# DUE3DOM_MINI_rev2_21022017-1546.net
KiCad netlist of a schematic drawn in EAGLE
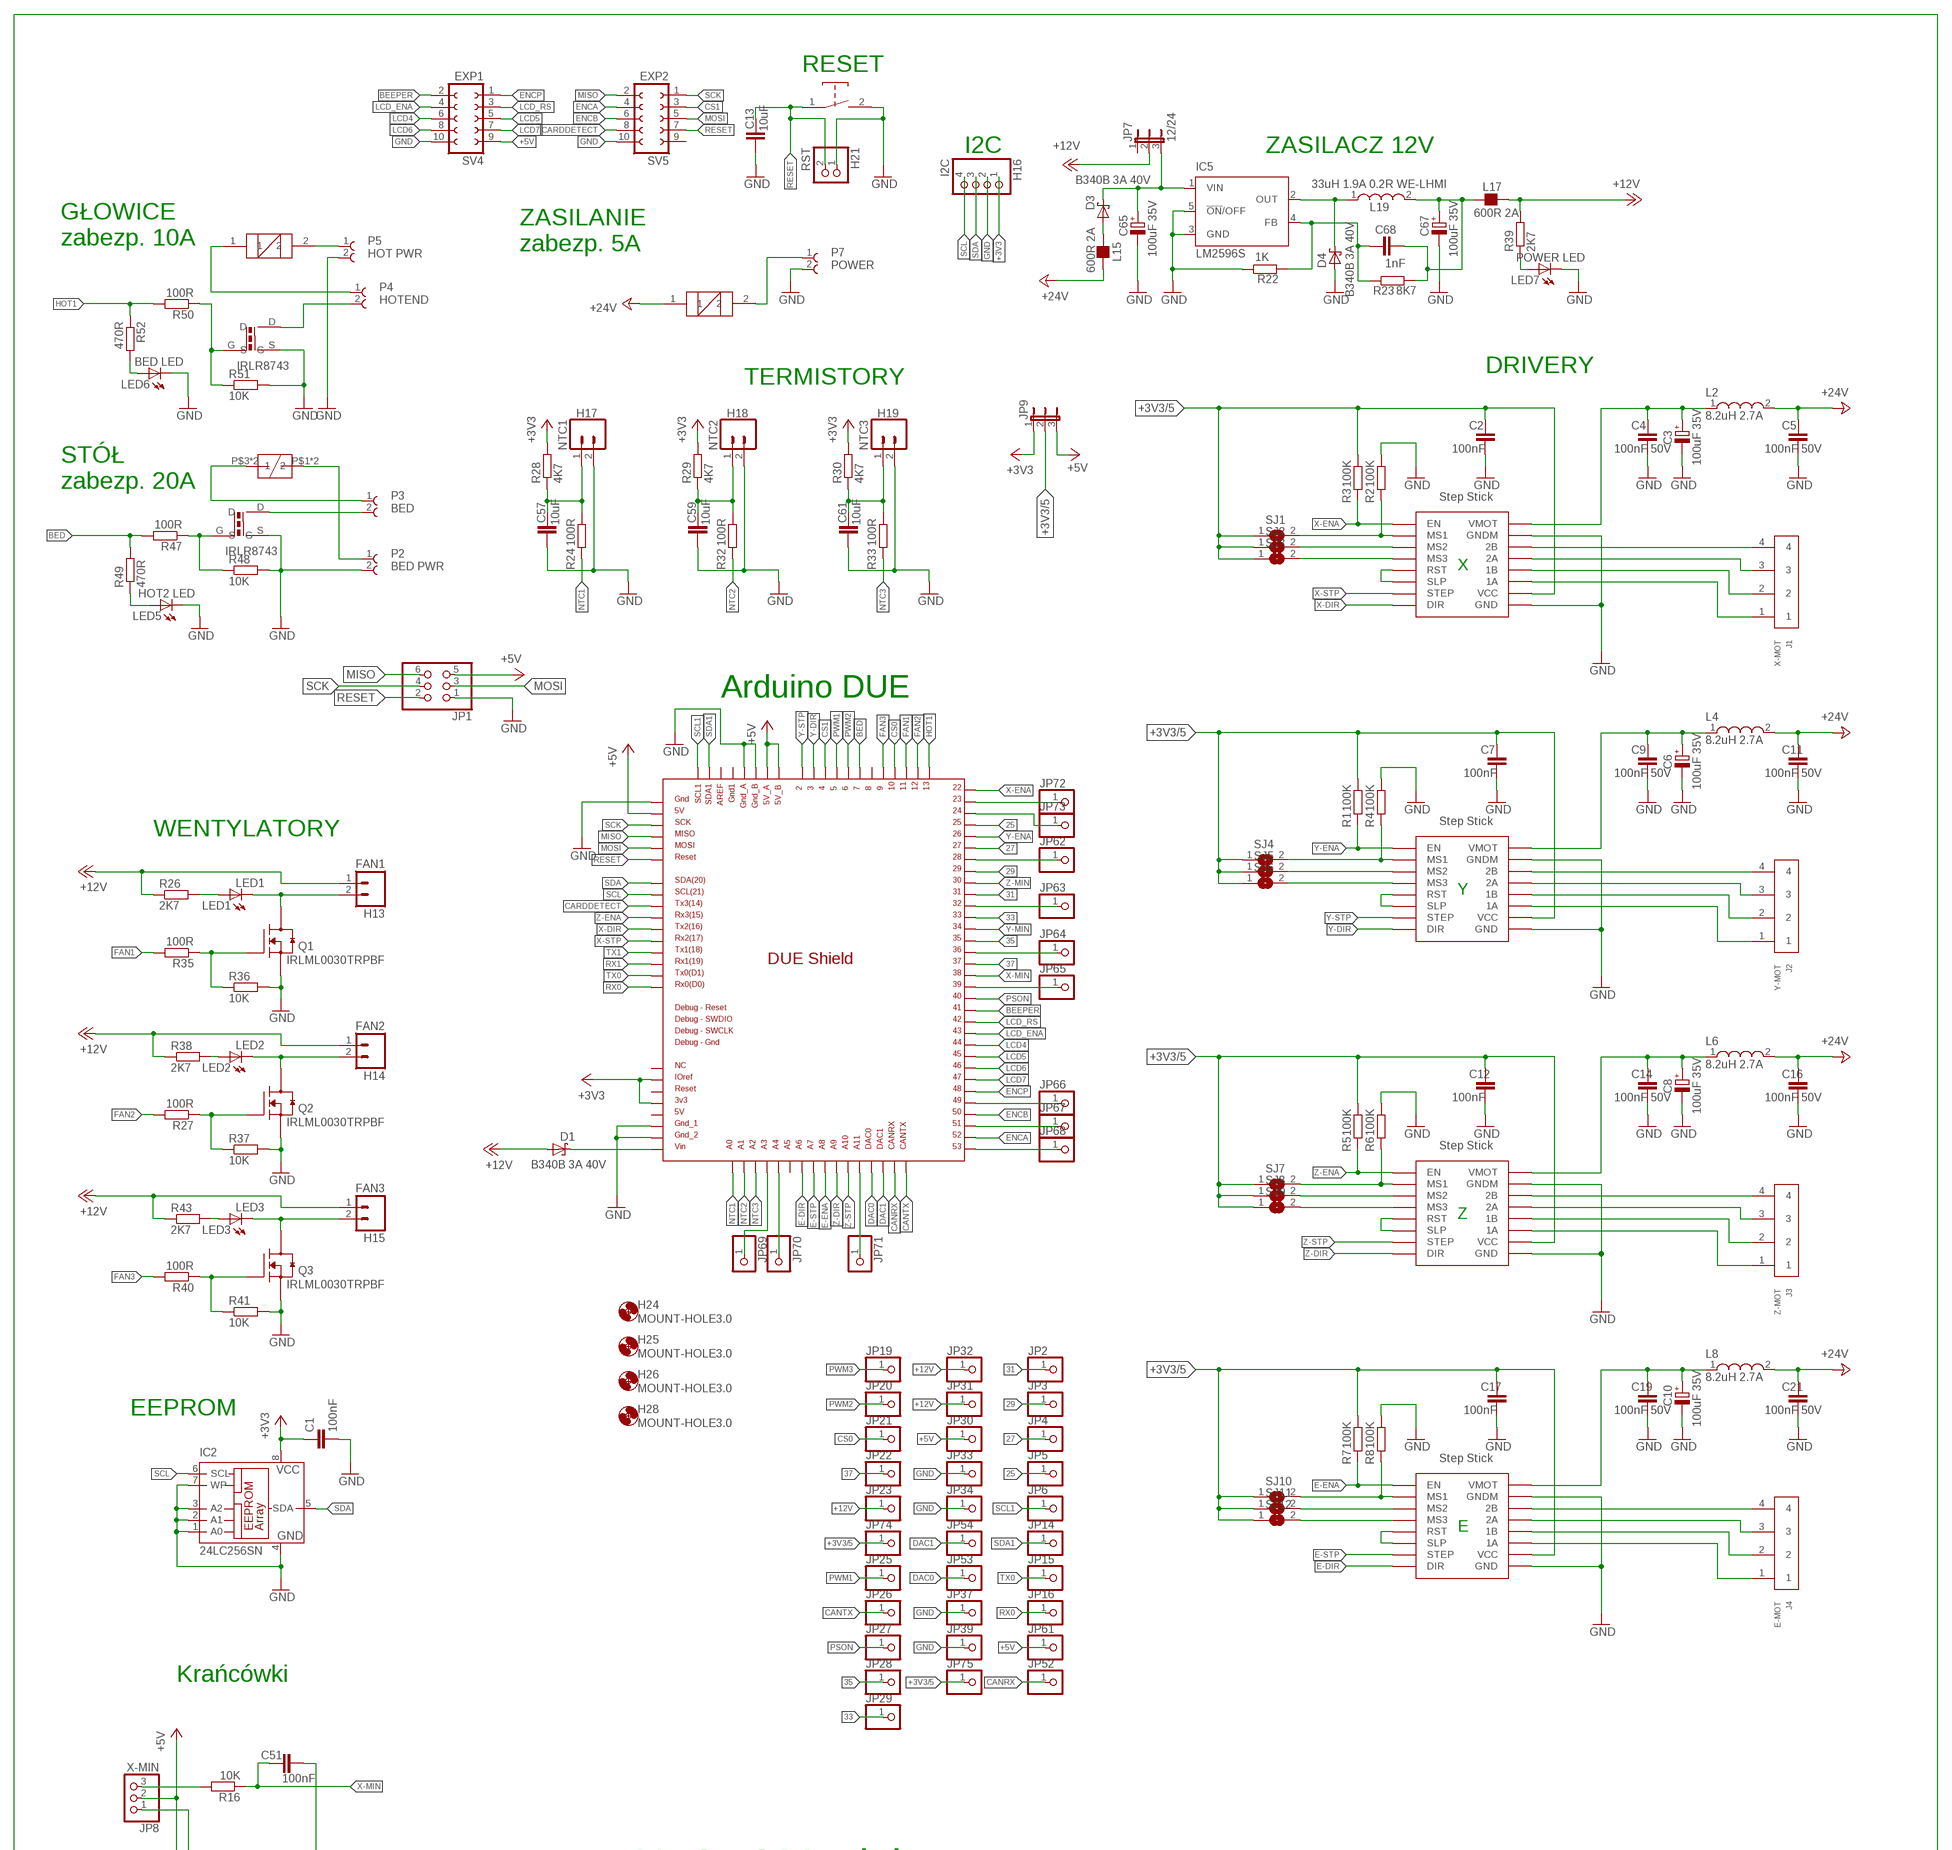
[diagram p0: schematic, sheet 1, part 1 of 2]
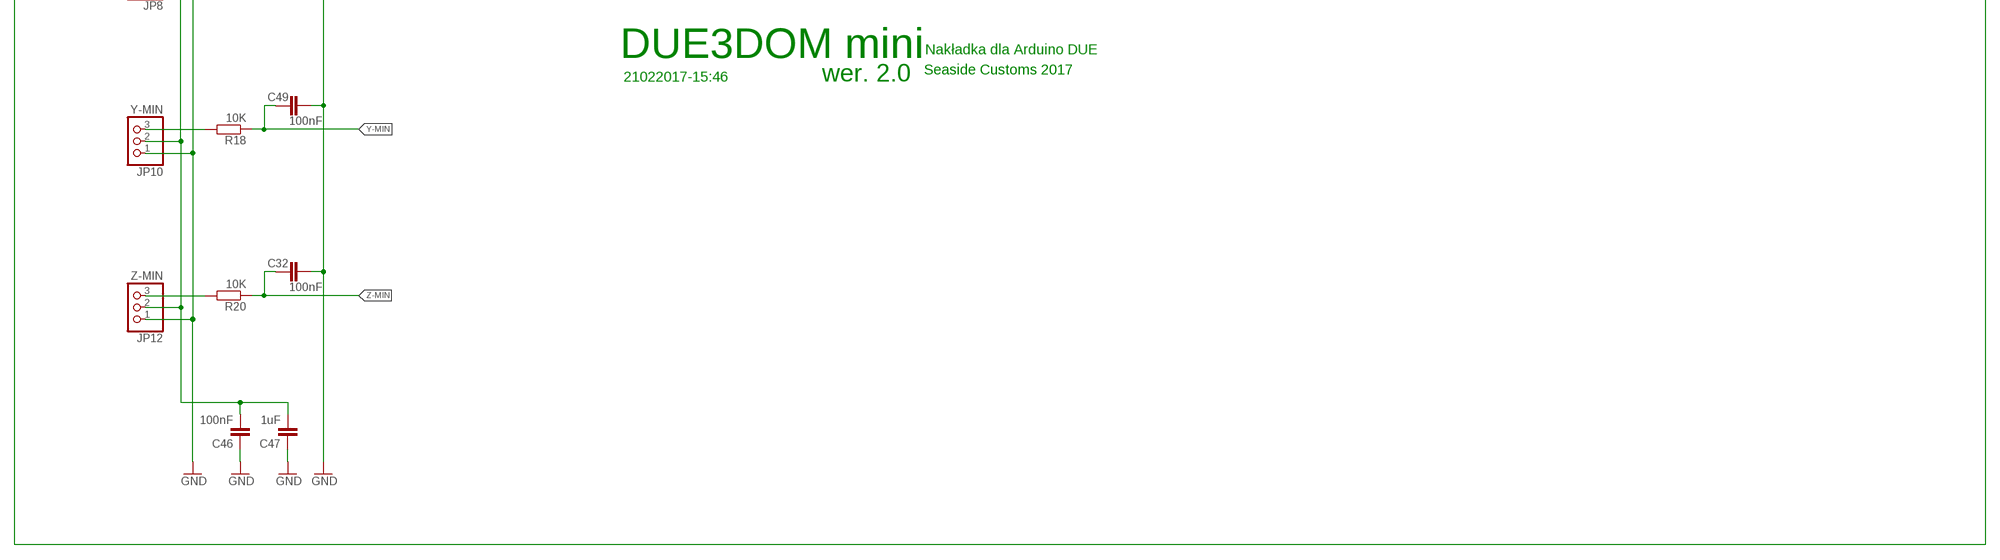
[diagram p1: schematic, sheet 1, part 2 of 2]

(export (version "E")
  (design (tool "Eeschema 10.0.6"))
  (components
    (comp (ref "C1")
      (value "100nF")
      (footprint "eagle-import:C0805")
      (libsource (lib "eagle-import") (part "C-EUC0805"))
    )
    (comp (ref "C2")
      (value "100nF")
      (footprint "eagle-import:C0805")
      (libsource (lib "eagle-import") (part "C-EUC0805"))
    )
    (comp (ref "C3")
      (value "100uF 35V")
      (footprint "eagle-import:PANASONIC_D")
      (libsource (lib "eagle-import") (part "CPOL-EUD"))
    )
    (comp (ref "C4")
      (value "100nF 50V")
      (footprint "eagle-import:C0805")
      (libsource (lib "eagle-import") (part "C-EUC0805"))
    )
    (comp (ref "C5")
      (value "100nF 50V")
      (footprint "eagle-import:C0805")
      (libsource (lib "eagle-import") (part "C-EUC0805"))
    )
    (comp (ref "C6")
      (value "100uF 35V")
      (footprint "eagle-import:PANASONIC_D")
      (libsource (lib "eagle-import") (part "CPOL-EUD"))
    )
    (comp (ref "C7")
      (value "100nF")
      (footprint "eagle-import:C0805")
      (libsource (lib "eagle-import") (part "C-EUC0805"))
    )
    (comp (ref "C8")
      (value "100uF 35V")
      (footprint "eagle-import:PANASONIC_D")
      (libsource (lib "eagle-import") (part "CPOL-EUD"))
    )
    (comp (ref "C9")
      (value "100nF 50V")
      (footprint "eagle-import:C0805")
      (libsource (lib "eagle-import") (part "C-EUC0805"))
    )
    (comp (ref "C10")
      (value "100uF 35V")
      (footprint "eagle-import:PANASONIC_D")
      (libsource (lib "eagle-import") (part "CPOL-EUD"))
    )
    (comp (ref "C11")
      (value "100nF 50V")
      (footprint "eagle-import:C0805")
      (libsource (lib "eagle-import") (part "C-EUC0805"))
    )
    (comp (ref "C12")
      (value "100nF")
      (footprint "eagle-import:C0805")
      (libsource (lib "eagle-import") (part "C-EUC0805"))
    )
    (comp (ref "C13")
      (value "10uF")
      (footprint "eagle-import:C0805")
      (libsource (lib "eagle-import") (part "C-EUC0805"))
    )
    (comp (ref "C14")
      (value "100nF 50V")
      (footprint "eagle-import:C0805")
      (libsource (lib "eagle-import") (part "C-EUC0805"))
    )
    (comp (ref "C16")
      (value "100nF 50V")
      (footprint "eagle-import:C0805")
      (libsource (lib "eagle-import") (part "C-EUC0805"))
    )
    (comp (ref "C17")
      (value "100nF")
      (footprint "eagle-import:C0805")
      (libsource (lib "eagle-import") (part "C-EUC0805"))
    )
    (comp (ref "C19")
      (value "100nF 50V")
      (footprint "eagle-import:C0805")
      (libsource (lib "eagle-import") (part "C-EUC0805"))
    )
    (comp (ref "C21")
      (value "100nF 50V")
      (footprint "eagle-import:C0805")
      (libsource (lib "eagle-import") (part "C-EUC0805"))
    )
    (comp (ref "C32")
      (value "100nF")
      (footprint "eagle-import:C0805")
      (libsource (lib "eagle-import") (part "C-EUC0805"))
    )
    (comp (ref "C46")
      (value "100nF")
      (footprint "eagle-import:C0805")
      (libsource (lib "eagle-import") (part "C-EUC0805"))
    )
    (comp (ref "C47")
      (value "1uF")
      (footprint "eagle-import:C0805")
      (libsource (lib "eagle-import") (part "C-EUC0805"))
    )
    (comp (ref "C49")
      (value "100nF")
      (footprint "eagle-import:C0805")
      (libsource (lib "eagle-import") (part "C-EUC0805"))
    )
    (comp (ref "C51")
      (value "100nF")
      (footprint "eagle-import:C0805")
      (libsource (lib "eagle-import") (part "C-EUC0805"))
    )
    (comp (ref "C57")
      (value "10uF")
      (footprint "eagle-import:C0805")
      (libsource (lib "eagle-import") (part "C-EUC0805"))
    )
    (comp (ref "C59")
      (value "10uF")
      (footprint "eagle-import:C0805")
      (libsource (lib "eagle-import") (part "C-EUC0805"))
    )
    (comp (ref "C61")
      (value "10uF")
      (footprint "eagle-import:C0805")
      (libsource (lib "eagle-import") (part "C-EUC0805"))
    )
    (comp (ref "C65")
      (value "100uF 35V")
      (footprint "eagle-import:E2,5-6")
      (libsource (lib "eagle-import") (part "CPOL-EUE2.5-6"))
    )
    (comp (ref "C67")
      (value "100uF 35V")
      (footprint "eagle-import:E2,5-6")
      (libsource (lib "eagle-import") (part "CPOL-EUE2.5-6"))
    )
    (comp (ref "C68")
      (value "1nF")
      (footprint "eagle-import:C0805")
      (libsource (lib "eagle-import") (part "C-EUC0805"))
    )
    (comp (ref "D1")
      (value "B340B 3A 40V")
      (footprint "eagle-import:SMB")
      (libsource (lib "eagle-import") (part "SCHOTTKY-DIODESMD"))
    )
    (comp (ref "D3")
      (value "B340B 3A 40V")
      (footprint "eagle-import:SMB")
      (libsource (lib "eagle-import") (part "SCHOTTKY-DIODESMD"))
    )
    (comp (ref "D4")
      (value "B340B 3A 40V")
      (footprint "eagle-import:SMB")
      (libsource (lib "eagle-import") (part "SCHOTTKY-DIODESMD"))
    )
    (comp (ref "FET1")
      (value "DPAK_N-CHANNEL_MOSFET")
      (footprint "eagle-import:DPAK_N-CHANNEL_MOSFET")
      (libsource (lib "eagle-import") (part "DPAK_N-CHANNEL_MOSFET"))
    )
    (comp (ref "FET2")
      (value "DPAK_N-CHANNEL_MOSFET")
      (footprint "eagle-import:DPAK_N-CHANNEL_MOSFET")
      (libsource (lib "eagle-import") (part "DPAK_N-CHANNEL_MOSFET"))
    )
    (comp (ref "FUSE")
      (value "GNIAZDO_BEZPIECZNIKA_MINI_CHRL")
      (footprint "eagle-import:FUSE_MINI_CHRL")
      (libsource (lib "eagle-import") (part "GNIAZDO_BEZPIECZNIKA_MINI_CHRL"))
    )
    (comp (ref "H13")
      (value "FAN1")
      (footprint "eagle-import:MOLEX-1X2")
      (libsource (lib "eagle-import") (part "M02POLAR"))
    )
    (comp (ref "H14")
      (value "FAN2")
      (footprint "eagle-import:MOLEX-1X2")
      (libsource (lib "eagle-import") (part "M02POLAR"))
    )
    (comp (ref "H15")
      (value "FAN3")
      (footprint "eagle-import:MOLEX-1X2")
      (libsource (lib "eagle-import") (part "M02POLAR"))
    )
    (comp (ref "H16")
      (value "I2C")
      (footprint "eagle-import:1X04")
      (libsource (lib "eagle-import") (part "PINHD-1X4"))
    )
    (comp (ref "H17")
      (value "NTC1")
      (footprint "eagle-import:MOLEX-1X2")
      (libsource (lib "eagle-import") (part "M02POLAR"))
    )
    (comp (ref "H18")
      (value "NTC2")
      (footprint "eagle-import:MOLEX-1X2")
      (libsource (lib "eagle-import") (part "M02POLAR"))
    )
    (comp (ref "H19")
      (value "NTC3")
      (footprint "eagle-import:MOLEX-1X2")
      (libsource (lib "eagle-import") (part "M02POLAR"))
    )
    (comp (ref "H21")
      (value "RST")
      (footprint "eagle-import:1X02")
      (libsource (lib "eagle-import") (part "PINHD-1X2"))
    )
    (comp (ref "H24")
      (value "MOUNT-HOLE3.0")
      (footprint "eagle-import:3,0")
      (libsource (lib "eagle-import") (part "MOUNT-HOLE3.0"))
    )
    (comp (ref "H25")
      (value "MOUNT-HOLE3.0")
      (footprint "eagle-import:3,0")
      (libsource (lib "eagle-import") (part "MOUNT-HOLE3.0"))
    )
    (comp (ref "H26")
      (value "MOUNT-HOLE3.0")
      (footprint "eagle-import:3,0")
      (libsource (lib "eagle-import") (part "MOUNT-HOLE3.0"))
    )
    (comp (ref "H28")
      (value "MOUNT-HOLE3.0")
      (footprint "eagle-import:3,0")
      (libsource (lib "eagle-import") (part "MOUNT-HOLE3.0"))
    )
    (comp (ref "IC2")
      (value "24LC256SN")
      (footprint "eagle-import:SO-08")
      (fields (field (name "MF") "MICROCHIP") (field (name "MPN") "24LC256-I/SN"))
      (libsource (lib "eagle-import") (part "24SNLC256"))
    )
    (comp (ref "IC5")
      (value "LM2596S")
      (footprint "eagle-import:TO263-5")
      (fields (field (name "MF") "NATIONAL SEMICONDUCTOR") (field (name "MPN") "LM2596S-ADJ/NOPB"))
      (libsource (lib "eagle-import") (part "LM2596S"))
    )
    (comp (ref "J1")
      (value "X-MOT")
      (footprint "eagle-import:66100411622")
      (libsource (lib "eagle-import") (part "66100411622"))
    )
    (comp (ref "J2")
      (value "Y-MOT")
      (footprint "eagle-import:66100411622")
      (libsource (lib "eagle-import") (part "66100411622"))
    )
    (comp (ref "J3")
      (value "Z-MOT")
      (footprint "eagle-import:66100411622")
      (libsource (lib "eagle-import") (part "66100411622"))
    )
    (comp (ref "J4")
      (value "E-MOT")
      (footprint "eagle-import:66100411622")
      (libsource (lib "eagle-import") (part "66100411622"))
    )
    (comp (ref "JP1")
      (value "PINHD-2X3")
      (footprint "eagle-import:2X03")
      (libsource (lib "eagle-import") (part "PINHD-2X3"))
    )
    (comp (ref "JP2")
      (value "PINHD-1X1")
      (footprint "eagle-import:1X01")
      (libsource (lib "eagle-import") (part "PINHD-1X1"))
    )
    (comp (ref "JP3")
      (value "PINHD-1X1")
      (footprint "eagle-import:1X01")
      (libsource (lib "eagle-import") (part "PINHD-1X1"))
    )
    (comp (ref "JP4")
      (value "PINHD-1X1")
      (footprint "eagle-import:1X01")
      (libsource (lib "eagle-import") (part "PINHD-1X1"))
    )
    (comp (ref "JP5")
      (value "PINHD-1X1")
      (footprint "eagle-import:1X01")
      (libsource (lib "eagle-import") (part "PINHD-1X1"))
    )
    (comp (ref "JP6")
      (value "PINHD-1X1")
      (footprint "eagle-import:1X01")
      (libsource (lib "eagle-import") (part "PINHD-1X1"))
    )
    (comp (ref "JP7")
      (value "12/24")
      (footprint "eagle-import:JP2")
      (libsource (lib "eagle-import") (part "JP2E"))
    )
    (comp (ref "JP8")
      (value "X-MIN")
      (footprint "eagle-import:1X03")
      (libsource (lib "eagle-import") (part "PINHD-1X3"))
    )
    (comp (ref "JP9")
      (value "JP2E")
      (footprint "eagle-import:JP2")
      (libsource (lib "eagle-import") (part "JP2E"))
    )
    (comp (ref "JP10")
      (value "Y-MIN")
      (footprint "eagle-import:1X03")
      (libsource (lib "eagle-import") (part "PINHD-1X3"))
    )
    (comp (ref "JP12")
      (value "Z-MIN")
      (footprint "eagle-import:1X03")
      (libsource (lib "eagle-import") (part "PINHD-1X3"))
    )
    (comp (ref "JP14")
      (value "PINHD-1X1")
      (footprint "eagle-import:1X01")
      (libsource (lib "eagle-import") (part "PINHD-1X1"))
    )
    (comp (ref "JP15")
      (value "PINHD-1X1")
      (footprint "eagle-import:1X01")
      (libsource (lib "eagle-import") (part "PINHD-1X1"))
    )
    (comp (ref "JP16")
      (value "PINHD-1X1")
      (footprint "eagle-import:1X01")
      (libsource (lib "eagle-import") (part "PINHD-1X1"))
    )
    (comp (ref "JP19")
      (value "PINHD-1X1")
      (footprint "eagle-import:1X01")
      (libsource (lib "eagle-import") (part "PINHD-1X1"))
    )
    (comp (ref "JP20")
      (value "PINHD-1X1")
      (footprint "eagle-import:1X01")
      (libsource (lib "eagle-import") (part "PINHD-1X1"))
    )
    (comp (ref "JP21")
      (value "PINHD-1X1")
      (footprint "eagle-import:1X01")
      (libsource (lib "eagle-import") (part "PINHD-1X1"))
    )
    (comp (ref "JP22")
      (value "PINHD-1X1")
      (footprint "eagle-import:1X01")
      (libsource (lib "eagle-import") (part "PINHD-1X1"))
    )
    (comp (ref "JP23")
      (value "PINHD-1X1")
      (footprint "eagle-import:1X01")
      (libsource (lib "eagle-import") (part "PINHD-1X1"))
    )
    (comp (ref "JP25")
      (value "PINHD-1X1")
      (footprint "eagle-import:1X01")
      (libsource (lib "eagle-import") (part "PINHD-1X1"))
    )
    (comp (ref "JP26")
      (value "PINHD-1X1")
      (footprint "eagle-import:1X01")
      (libsource (lib "eagle-import") (part "PINHD-1X1"))
    )
    (comp (ref "JP27")
      (value "PINHD-1X1")
      (footprint "eagle-import:1X01")
      (libsource (lib "eagle-import") (part "PINHD-1X1"))
    )
    (comp (ref "JP28")
      (value "PINHD-1X1")
      (footprint "eagle-import:1X01")
      (libsource (lib "eagle-import") (part "PINHD-1X1"))
    )
    (comp (ref "JP29")
      (value "PINHD-1X1")
      (footprint "eagle-import:1X01")
      (libsource (lib "eagle-import") (part "PINHD-1X1"))
    )
    (comp (ref "JP30")
      (value "PINHD-1X1")
      (footprint "eagle-import:1X01")
      (libsource (lib "eagle-import") (part "PINHD-1X1"))
    )
    (comp (ref "JP31")
      (value "PINHD-1X1")
      (footprint "eagle-import:1X01")
      (libsource (lib "eagle-import") (part "PINHD-1X1"))
    )
    (comp (ref "JP32")
      (value "PINHD-1X1")
      (footprint "eagle-import:1X01")
      (libsource (lib "eagle-import") (part "PINHD-1X1"))
    )
    (comp (ref "JP33")
      (value "PINHD-1X1")
      (footprint "eagle-import:1X01")
      (libsource (lib "eagle-import") (part "PINHD-1X1"))
    )
    (comp (ref "JP34")
      (value "PINHD-1X1")
      (footprint "eagle-import:1X01")
      (libsource (lib "eagle-import") (part "PINHD-1X1"))
    )
    (comp (ref "JP37")
      (value "PINHD-1X1")
      (footprint "eagle-import:1X01")
      (libsource (lib "eagle-import") (part "PINHD-1X1"))
    )
    (comp (ref "JP39")
      (value "PINHD-1X1")
      (footprint "eagle-import:1X01")
      (libsource (lib "eagle-import") (part "PINHD-1X1"))
    )
    (comp (ref "JP52")
      (value "PINHD-1X1")
      (footprint "eagle-import:1X01")
      (libsource (lib "eagle-import") (part "PINHD-1X1"))
    )
    (comp (ref "JP53")
      (value "PINHD-1X1")
      (footprint "eagle-import:1X01")
      (libsource (lib "eagle-import") (part "PINHD-1X1"))
    )
    (comp (ref "JP54")
      (value "PINHD-1X1")
      (footprint "eagle-import:1X01")
      (libsource (lib "eagle-import") (part "PINHD-1X1"))
    )
    (comp (ref "JP61")
      (value "PINHD-1X1")
      (footprint "eagle-import:1X01")
      (libsource (lib "eagle-import") (part "PINHD-1X1"))
    )
    (comp (ref "JP62")
      (value "PINHD-1X1")
      (footprint "eagle-import:1X01")
      (libsource (lib "eagle-import") (part "PINHD-1X1"))
    )
    (comp (ref "JP63")
      (value "PINHD-1X1")
      (footprint "eagle-import:1X01")
      (libsource (lib "eagle-import") (part "PINHD-1X1"))
    )
    (comp (ref "JP64")
      (value "PINHD-1X1")
      (footprint "eagle-import:1X01")
      (libsource (lib "eagle-import") (part "PINHD-1X1"))
    )
    (comp (ref "JP65")
      (value "PINHD-1X1")
      (footprint "eagle-import:1X01")
      (libsource (lib "eagle-import") (part "PINHD-1X1"))
    )
    (comp (ref "JP66")
      (value "PINHD-1X1")
      (footprint "eagle-import:1X01")
      (libsource (lib "eagle-import") (part "PINHD-1X1"))
    )
    (comp (ref "JP67")
      (value "PINHD-1X1")
      (footprint "eagle-import:1X01")
      (libsource (lib "eagle-import") (part "PINHD-1X1"))
    )
    (comp (ref "JP68")
      (value "PINHD-1X1")
      (footprint "eagle-import:1X01")
      (libsource (lib "eagle-import") (part "PINHD-1X1"))
    )
    (comp (ref "JP69")
      (value "PINHD-1X1")
      (footprint "eagle-import:1X01")
      (libsource (lib "eagle-import") (part "PINHD-1X1"))
    )
    (comp (ref "JP70")
      (value "PINHD-1X1")
      (footprint "eagle-import:1X01")
      (libsource (lib "eagle-import") (part "PINHD-1X1"))
    )
    (comp (ref "JP71")
      (value "PINHD-1X1")
      (footprint "eagle-import:1X01")
      (libsource (lib "eagle-import") (part "PINHD-1X1"))
    )
    (comp (ref "JP72")
      (value "PINHD-1X1")
      (footprint "eagle-import:1X01")
      (libsource (lib "eagle-import") (part "PINHD-1X1"))
    )
    (comp (ref "JP73")
      (value "PINHD-1X1")
      (footprint "eagle-import:1X01")
      (libsource (lib "eagle-import") (part "PINHD-1X1"))
    )
    (comp (ref "JP74")
      (value "PINHD-1X1")
      (footprint "eagle-import:1X01")
      (libsource (lib "eagle-import") (part "PINHD-1X1"))
    )
    (comp (ref "JP75")
      (value "PINHD-1X1")
      (footprint "eagle-import:1X01")
      (libsource (lib "eagle-import") (part "PINHD-1X1"))
    )
    (comp (ref "L2")
      (value "8.2uH 2.7A")
      (footprint "eagle-import:WE-PD_7332_7345_PLASTIC_BASE")
      (libsource (lib "eagle-import") (part "WE-PD_7332/7345_PLASTIC_BASE"))
    )
    (comp (ref "L4")
      (value "8.2uH 2.7A")
      (footprint "eagle-import:WE-PD_7332_7345_PLASTIC_BASE")
      (libsource (lib "eagle-import") (part "WE-PD_7332/7345_PLASTIC_BASE"))
    )
    (comp (ref "L6")
      (value "8.2uH 2.7A")
      (footprint "eagle-import:WE-PD_7332_7345_PLASTIC_BASE")
      (libsource (lib "eagle-import") (part "WE-PD_7332/7345_PLASTIC_BASE"))
    )
    (comp (ref "L8")
      (value "8.2uH 2.7A")
      (footprint "eagle-import:WE-PD_7332_7345_PLASTIC_BASE")
      (libsource (lib "eagle-import") (part "WE-PD_7332/7345_PLASTIC_BASE"))
    )
    (comp (ref "L15")
      (value "600R 2A")
      (footprint "eagle-import:L1206")
      (libsource (lib "eagle-import") (part "FB_1206"))
    )
    (comp (ref "L17")
      (value "600R 2A")
      (footprint "eagle-import:L1206")
      (libsource (lib "eagle-import") (part "FB_1206"))
    )
    (comp (ref "L19")
      (value "33uH 1.9A 0.2R WE-LHMI")
      (footprint "eagle-import:WE-LHMI_7030_7050")
      (libsource (lib "eagle-import") (part "WE-LHMI_7030/7050"))
    )
    (comp (ref "LED1")
      (value "LED1")
      (footprint "eagle-import:LED_0805_BIVAR_VLP-250-F")
      (libsource (lib "eagle-import") (part "LED_0805_BIVAR_VLP-250-F"))
    )
    (comp (ref "LED2")
      (value "LED2")
      (footprint "eagle-import:LED_0805_BIVAR_VLP-250-F")
      (libsource (lib "eagle-import") (part "LED_0805_BIVAR_VLP-250-F"))
    )
    (comp (ref "LED3")
      (value "LED3")
      (footprint "eagle-import:LED_0805_BIVAR_VLP-250-F")
      (libsource (lib "eagle-import") (part "LED_0805_BIVAR_VLP-250-F"))
    )
    (comp (ref "LED5")
      (value "HOT2 LED")
      (footprint "eagle-import:LED_0805_BIVAR_VLP-250-F")
      (libsource (lib "eagle-import") (part "LED_0805_BIVAR_VLP-250-F"))
    )
    (comp (ref "LED6")
      (value "BED LED")
      (footprint "eagle-import:LED_0805_BIVAR_VLP-250-F")
      (libsource (lib "eagle-import") (part "LED_0805_BIVAR_VLP-250-F"))
    )
    (comp (ref "LED7")
      (value "POWER LED")
      (footprint "eagle-import:LED_0805_BIVAR_VLP-250-F")
      (libsource (lib "eagle-import") (part "LED_0805_BIVAR_VLP-250-F"))
    )
    (comp (ref "P2")
      (value "BED PWR")
      (footprint "eagle-import:691241710002")
      (libsource (lib "eagle-import") (part "691241710002"))
    )
    (comp (ref "P3")
      (value "BED")
      (footprint "eagle-import:691241710002")
      (libsource (lib "eagle-import") (part "691241710002"))
    )
    (comp (ref "P4")
      (value "HOTEND")
      (footprint "eagle-import:691241710002")
      (libsource (lib "eagle-import") (part "691241710002"))
    )
    (comp (ref "P5")
      (value "HOT PWR")
      (footprint "eagle-import:691241710002")
      (libsource (lib "eagle-import") (part "691241710002"))
    )
    (comp (ref "P7")
      (value "POWER")
      (footprint "eagle-import:691241710002")
      (libsource (lib "eagle-import") (part "691241710002"))
    )
    (comp (ref "Q1")
      (value "IRLML0030TRPBF")
      (footprint "eagle-import:SOT95P280X135-3N")
      (libsource (lib "eagle-import") (part "MOSFET-NCH_SOT-23"))
    )
    (comp (ref "Q2")
      (value "IRLML0030TRPBF")
      (footprint "eagle-import:SOT95P280X135-3N")
      (libsource (lib "eagle-import") (part "MOSFET-NCH_SOT-23"))
    )
    (comp (ref "Q3")
      (value "IRLML0030TRPBF")
      (footprint "eagle-import:SOT95P280X135-3N")
      (libsource (lib "eagle-import") (part "MOSFET-NCH_SOT-23"))
    )
    (comp (ref "R1")
      (value "100K")
      (footprint "eagle-import:R0805")
      (libsource (lib "eagle-import") (part "R-EU_R0805"))
    )
    (comp (ref "R2")
      (value "100K")
      (footprint "eagle-import:R0805")
      (libsource (lib "eagle-import") (part "R-EU_R0805"))
    )
    (comp (ref "R3")
      (value "100K")
      (footprint "eagle-import:R0805")
      (libsource (lib "eagle-import") (part "R-EU_R0805"))
    )
    (comp (ref "R4")
      (value "100K")
      (footprint "eagle-import:R0805")
      (libsource (lib "eagle-import") (part "R-EU_R0805"))
    )
    (comp (ref "R5")
      (value "100K")
      (footprint "eagle-import:R0805")
      (libsource (lib "eagle-import") (part "R-EU_R0805"))
    )
    (comp (ref "R6")
      (value "100K")
      (footprint "eagle-import:R0805")
      (libsource (lib "eagle-import") (part "R-EU_R0805"))
    )
    (comp (ref "R7")
      (value "100K")
      (footprint "eagle-import:R0805")
      (libsource (lib "eagle-import") (part "R-EU_R0805"))
    )
    (comp (ref "R8")
      (value "100K")
      (footprint "eagle-import:R0805")
      (libsource (lib "eagle-import") (part "R-EU_R0805"))
    )
    (comp (ref "R16")
      (value "10K")
      (footprint "eagle-import:R0805")
      (libsource (lib "eagle-import") (part "R-EU_R0805"))
    )
    (comp (ref "R18")
      (value "10K")
      (footprint "eagle-import:R0805")
      (libsource (lib "eagle-import") (part "R-EU_R0805"))
    )
    (comp (ref "R20")
      (value "10K")
      (footprint "eagle-import:R0805")
      (libsource (lib "eagle-import") (part "R-EU_R0805"))
    )
    (comp (ref "R22")
      (value "1K")
      (footprint "eagle-import:R0805")
      (libsource (lib "eagle-import") (part "R-EU_R0805"))
    )
    (comp (ref "R23")
      (value "8K7")
      (footprint "eagle-import:R0805")
      (libsource (lib "eagle-import") (part "R-EU_R0805"))
    )
    (comp (ref "R24")
      (value "100R")
      (footprint "eagle-import:R0805")
      (libsource (lib "eagle-import") (part "R-EU_R0805"))
    )
    (comp (ref "R26")
      (value "2K7")
      (footprint "eagle-import:R0805")
      (libsource (lib "eagle-import") (part "R-EU_R0805"))
    )
    (comp (ref "R27")
      (value "100R")
      (footprint "eagle-import:R0805")
      (libsource (lib "eagle-import") (part "R-EU_R0805"))
    )
    (comp (ref "R28")
      (value "4K7")
      (footprint "eagle-import:R0805")
      (libsource (lib "eagle-import") (part "R-EU_R0805"))
    )
    (comp (ref "R29")
      (value "4K7")
      (footprint "eagle-import:R0805")
      (libsource (lib "eagle-import") (part "R-EU_R0805"))
    )
    (comp (ref "R30")
      (value "4K7")
      (footprint "eagle-import:R0805")
      (libsource (lib "eagle-import") (part "R-EU_R0805"))
    )
    (comp (ref "R32")
      (value "100R")
      (footprint "eagle-import:R0805")
      (libsource (lib "eagle-import") (part "R-EU_R0805"))
    )
    (comp (ref "R33")
      (value "100R")
      (footprint "eagle-import:R0805")
      (libsource (lib "eagle-import") (part "R-EU_R0805"))
    )
    (comp (ref "R35")
      (value "100R")
      (footprint "eagle-import:R0805")
      (libsource (lib "eagle-import") (part "R-EU_R0805"))
    )
    (comp (ref "R36")
      (value "10K")
      (footprint "eagle-import:R0805")
      (libsource (lib "eagle-import") (part "R-EU_R0805"))
    )
    (comp (ref "R37")
      (value "10K")
      (footprint "eagle-import:R0805")
      (libsource (lib "eagle-import") (part "R-EU_R0805"))
    )
    (comp (ref "R38")
      (value "2K7")
      (footprint "eagle-import:R0805")
      (libsource (lib "eagle-import") (part "R-EU_R0805"))
    )
    (comp (ref "R39")
      (value "2K7")
      (footprint "eagle-import:R0805")
      (libsource (lib "eagle-import") (part "R-EU_R0805"))
    )
    (comp (ref "R40")
      (value "100R")
      (footprint "eagle-import:R0805")
      (libsource (lib "eagle-import") (part "R-EU_R0805"))
    )
    (comp (ref "R41")
      (value "10K")
      (footprint "eagle-import:R0805")
      (libsource (lib "eagle-import") (part "R-EU_R0805"))
    )
    (comp (ref "R43")
      (value "2K7")
      (footprint "eagle-import:R0805")
      (libsource (lib "eagle-import") (part "R-EU_R0805"))
    )
    (comp (ref "R47")
      (value "100R")
      (footprint "eagle-import:R0805")
      (libsource (lib "eagle-import") (part "R-EU_R0805"))
    )
    (comp (ref "R48")
      (value "10K")
      (footprint "eagle-import:R0805")
      (libsource (lib "eagle-import") (part "R-EU_R0805"))
    )
    (comp (ref "R49")
      (value "470R")
      (footprint "eagle-import:R0805")
      (libsource (lib "eagle-import") (part "R-EU_R0805"))
    )
    (comp (ref "R50")
      (value "100R")
      (footprint "eagle-import:R0805")
      (libsource (lib "eagle-import") (part "R-EU_R0805"))
    )
    (comp (ref "R51")
      (value "10K")
      (footprint "eagle-import:R0805")
      (libsource (lib "eagle-import") (part "R-EU_R0805"))
    )
    (comp (ref "R52")
      (value "470R")
      (footprint "eagle-import:R0805")
      (libsource (lib "eagle-import") (part "R-EU_R0805"))
    )
    (comp (ref "RESET")
      (value "RESET")
      (footprint "eagle-import:WIDE_TACT")
      (libsource (lib "eagle-import") (part "WIDE_TACT"))
    )
    (comp (ref "SJ1") (value "SJ") (footprint "eagle-import:SJ") (libsource (lib "eagle-import") (part "SJ")))
    (comp (ref "SJ2") (value "SJ") (footprint "eagle-import:SJ") (libsource (lib "eagle-import") (part "SJ")))
    (comp (ref "SJ3") (value "SJ") (footprint "eagle-import:SJ") (libsource (lib "eagle-import") (part "SJ")))
    (comp (ref "SJ4") (value "SJ") (footprint "eagle-import:SJ") (libsource (lib "eagle-import") (part "SJ")))
    (comp (ref "SJ5") (value "SJ") (footprint "eagle-import:SJ") (libsource (lib "eagle-import") (part "SJ")))
    (comp (ref "SJ6") (value "SJ") (footprint "eagle-import:SJ") (libsource (lib "eagle-import") (part "SJ")))
    (comp (ref "SJ7") (value "SJ") (footprint "eagle-import:SJ") (libsource (lib "eagle-import") (part "SJ")))
    (comp (ref "SJ8") (value "SJ") (footprint "eagle-import:SJ") (libsource (lib "eagle-import") (part "SJ")))
    (comp (ref "SJ9") (value "SJ") (footprint "eagle-import:SJ") (libsource (lib "eagle-import") (part "SJ")))
    (comp (ref "SJ10")
      (value "SJ")
      (footprint "eagle-import:SJ")
      (libsource (lib "eagle-import") (part "SJ"))
    )
    (comp (ref "SJ11")
      (value "SJ")
      (footprint "eagle-import:SJ")
      (libsource (lib "eagle-import") (part "SJ"))
    )
    (comp (ref "SJ12")
      (value "SJ")
      (footprint "eagle-import:SJ")
      (libsource (lib "eagle-import") (part "SJ"))
    )
    (comp (ref "STEPSTICK-X")
      (value "STEP-STICK")
      (footprint "eagle-import:STEP-STICK")
      (libsource (lib "eagle-import") (part "STEP-STICK"))
    )
    (comp (ref "STEPSTICK-Y")
      (value "STEP-STICK")
      (footprint "eagle-import:STEP-STICK")
      (libsource (lib "eagle-import") (part "STEP-STICK"))
    )
    (comp (ref "STEPSTICK-Z1")
      (value "STEP-STICK")
      (footprint "eagle-import:STEP-STICK")
      (libsource (lib "eagle-import") (part "STEP-STICK"))
    )
    (comp (ref "STEPSTICK-Z2")
      (value "STEP-STICK")
      (footprint "eagle-import:STEP-STICK")
      (libsource (lib "eagle-import") (part "STEP-STICK"))
    )
    (comp (ref "SV4")
      (value "EXP1")
      (footprint "eagle-import:FE05-2")
      (libsource (lib "eagle-import") (part "FE05-2"))
    )
    (comp (ref "SV5")
      (value "EXP2")
      (footprint "eagle-import:FE05-2")
      (libsource (lib "eagle-import") (part "FE05-2"))
    )
    (comp (ref "U$1")
      (value "DUE(NORMAL)")
      (footprint "eagle-import:DUE(NORMAL)")
      (libsource (lib "eagle-import") (part "DUE(NORMAL)"))
    )
    (comp (ref "U$2")
      (value "FUSE_1808")
      (footprint "eagle-import:FUSE_1808")
      (libsource (lib "eagle-import") (part "FUSE_1808"))
    )
    (comp (ref "U$3")
      (value "FUSE_1808")
      (footprint "eagle-import:FUSE_1808")
      (libsource (lib "eagle-import") (part "FUSE_1808"))
    )
  )
  (nets
    (net (code "1") (name "+3V3") (class "Default")
      (node (ref "C1") (pin "1") (pinfunction "1_1") (pintype "passive"))
      (node (ref "H16") (pin "1") (pinfunction "1_1") (pintype "passive"))
      (node (ref "IC2") (pin "8") (pinfunction "VCC_8") (pintype "power_in"))
      (node (ref "JP9") (pin "1") (pinfunction "1_1") (pintype "passive"))
      (node (ref "R28") (pin "2") (pinfunction "2_2") (pintype "passive"))
      (node (ref "R29") (pin "2") (pinfunction "2_2") (pintype "passive"))
      (node (ref "R30") (pin "2") (pinfunction "2_2") (pintype "passive"))
      (node (ref "U$1") (pin "3V3") (pinfunction "3V3_3V3") (pintype "bidirectional"))
      (node (ref "U$1") (pin "IOREF") (pinfunction "IOREF_IOREF") (pintype "bidirectional"))
    )
    (net (code "2") (name "+3V3{slash}5") (class "Default")
      (node (ref "C12") (pin "1") (pinfunction "1_1") (pintype "passive"))
      (node (ref "C17") (pin "1") (pinfunction "1_1") (pintype "passive"))
      (node (ref "C2") (pin "1") (pinfunction "1_1") (pintype "passive"))
      (node (ref "C7") (pin "1") (pinfunction "1_1") (pintype "passive"))
      (node (ref "JP74") (pin "1") (pinfunction "1_1") (pintype "passive"))
      (node (ref "JP75") (pin "1") (pinfunction "1_1") (pintype "passive"))
      (node (ref "JP9") (pin "2") (pinfunction "2_2") (pintype "passive"))
      (node (ref "R1") (pin "1") (pinfunction "1_1") (pintype "passive"))
      (node (ref "R3") (pin "1") (pinfunction "1_1") (pintype "passive"))
      (node (ref "R5") (pin "1") (pinfunction "1_1") (pintype "passive"))
      (node (ref "R7") (pin "1") (pinfunction "1_1") (pintype "passive"))
      (node (ref "SJ1") (pin "1") (pinfunction "1_1") (pintype "passive"))
      (node (ref "SJ10") (pin "1") (pinfunction "1_1") (pintype "passive"))
      (node (ref "SJ11") (pin "1") (pinfunction "1_1") (pintype "passive"))
      (node (ref "SJ12") (pin "1") (pinfunction "1_1") (pintype "passive"))
      (node (ref "SJ2") (pin "1") (pinfunction "1_1") (pintype "passive"))
      (node (ref "SJ3") (pin "1") (pinfunction "1_1") (pintype "passive"))
      (node (ref "SJ4") (pin "1") (pinfunction "1_1") (pintype "passive"))
      (node (ref "SJ5") (pin "1") (pinfunction "1_1") (pintype "passive"))
      (node (ref "SJ6") (pin "1") (pinfunction "1_1") (pintype "passive"))
      (node (ref "SJ7") (pin "1") (pinfunction "1_1") (pintype "passive"))
      (node (ref "SJ8") (pin "1") (pinfunction "1_1") (pintype "passive"))
      (node (ref "SJ9") (pin "1") (pinfunction "1_1") (pintype "passive"))
      (node (ref "STEPSTICK-X") (pin "VDD") (pinfunction "VCC_VDD") (pintype "bidirectional"))
      (node (ref "STEPSTICK-Y") (pin "VDD") (pinfunction "VCC_VDD") (pintype "bidirectional"))
      (node (ref "STEPSTICK-Z1") (pin "VDD") (pinfunction "VCC_VDD") (pintype "bidirectional"))
      (node (ref "STEPSTICK-Z2") (pin "VDD") (pinfunction "VCC_VDD") (pintype "bidirectional"))
    )
    (net (code "3") (name "+5V") (class "Default")
      (node (ref "C46") (pin "2") (pinfunction "2_2") (pintype "passive"))
      (node (ref "C47") (pin "2") (pinfunction "2_2") (pintype "passive"))
      (node (ref "JP1") (pin "5") (pinfunction "5_5") (pintype "passive"))
      (node (ref "JP10") (pin "2") (pinfunction "2_2") (pintype "passive"))
      (node (ref "JP12") (pin "2") (pinfunction "2_2") (pintype "passive"))
      (node (ref "JP30") (pin "1") (pinfunction "1_1") (pintype "passive"))
      (node (ref "JP61") (pin "1") (pinfunction "1_1") (pintype "passive"))
      (node (ref "JP8") (pin "2") (pinfunction "2_2") (pintype "passive"))
      (node (ref "JP9") (pin "3") (pinfunction "3_3") (pintype "passive"))
      (node (ref "SV4") (pin "9") (pinfunction "9_9") (pintype "passive"))
      (node (ref "U$1") (pin "5V_A") (pinfunction "5V_A_5V_A") (pintype "bidirectional"))
      (node (ref "U$1") (pin "5V_B") (pinfunction "5V_B_5V_B") (pintype "bidirectional"))
      (node (ref "U$1") (pin "GND_ICSP") (pinfunction "GND_ICSP_GND_ICSP") (pintype "bidirectional"))
    )
    (net (code "4") (name "+12V") (class "Default")
      (node (ref "D1") (pin "A") (pinfunction "A_A") (pintype "passive"))
      (node (ref "H13") (pin "1") (pinfunction "1_1") (pintype "passive"))
      (node (ref "H14") (pin "1") (pinfunction "1_1") (pintype "passive"))
      (node (ref "H15") (pin "1") (pinfunction "1_1") (pintype "passive"))
      (node (ref "JP23") (pin "1") (pinfunction "1_1") (pintype "passive"))
      (node (ref "JP31") (pin "1") (pinfunction "1_1") (pintype "passive"))
      (node (ref "JP32") (pin "1") (pinfunction "1_1") (pintype "passive"))
      (node (ref "JP7") (pin "2") (pinfunction "2_2") (pintype "passive"))
      (node (ref "L17") (pin "2") (pinfunction "2_2") (pintype "passive"))
      (node (ref "R26") (pin "1") (pinfunction "1_1") (pintype "passive"))
      (node (ref "R38") (pin "1") (pinfunction "1_1") (pintype "passive"))
      (node (ref "R39") (pin "2") (pinfunction "2_2") (pintype "passive"))
      (node (ref "R43") (pin "1") (pinfunction "1_1") (pintype "passive"))
    )
    (net (code "5") (name "+24V") (class "Default")
      (node (ref "C11") (pin "1") (pinfunction "1_1") (pintype "passive"))
      (node (ref "C16") (pin "1") (pinfunction "1_1") (pintype "passive"))
      (node (ref "C21") (pin "1") (pinfunction "1_1") (pintype "passive"))
      (node (ref "C5") (pin "1") (pinfunction "1_1") (pintype "passive"))
      (node (ref "L15") (pin "1") (pinfunction "1_1") (pintype "passive"))
      (node (ref "L2") (pin "2") (pinfunction "2_2") (pintype "passive"))
      (node (ref "L4") (pin "2") (pinfunction "2_2") (pintype "passive"))
      (node (ref "L6") (pin "2") (pinfunction "2_2") (pintype "passive"))
      (node (ref "L8") (pin "2") (pinfunction "2_2") (pintype "passive"))
      (node (ref "U$3") (pin "1") (pinfunction "1_1") (pintype "bidirectional"))
    )
    (net (code "6") (name "25") (class "Default")
      (node (ref "JP5") (pin "1") (pinfunction "1_1") (pintype "passive"))
      (node (ref "U$1") (pin "25") (pinfunction "25_25") (pintype "bidirectional"))
    )
    (net (code "7") (name "27") (class "Default")
      (node (ref "JP4") (pin "1") (pinfunction "1_1") (pintype "passive"))
      (node (ref "U$1") (pin "27") (pinfunction "27_27") (pintype "bidirectional"))
    )
    (net (code "8") (name "29") (class "Default")
      (node (ref "JP3") (pin "1") (pinfunction "1_1") (pintype "passive"))
      (node (ref "U$1") (pin "29") (pinfunction "29_29") (pintype "bidirectional"))
    )
    (net (code "9") (name "31") (class "Default")
      (node (ref "JP2") (pin "1") (pinfunction "1_1") (pintype "passive"))
      (node (ref "U$1") (pin "31") (pinfunction "31_31") (pintype "bidirectional"))
    )
    (net (code "10") (name "33") (class "Default")
      (node (ref "JP29") (pin "1") (pinfunction "1_1") (pintype "passive"))
      (node (ref "U$1") (pin "33") (pinfunction "33_33") (pintype "bidirectional"))
    )
    (net (code "11") (name "35") (class "Default")
      (node (ref "JP28") (pin "1") (pinfunction "1_1") (pintype "passive"))
      (node (ref "U$1") (pin "35") (pinfunction "35_35") (pintype "bidirectional"))
    )
    (net (code "12") (name "37") (class "Default")
      (node (ref "JP22") (pin "1") (pinfunction "1_1") (pintype "passive"))
      (node (ref "U$1") (pin "37") (pinfunction "37_37") (pintype "bidirectional"))
    )
    (net (code "13") (name "BED") (class "Default")
      (node (ref "R47") (pin "2") (pinfunction "2_2") (pintype "passive"))
      (node (ref "R49") (pin "2") (pinfunction "2_2") (pintype "passive"))
      (node (ref "U$1") (pin "7") (pinfunction "7_7") (pintype "bidirectional"))
    )
    (net (code "14") (name "BEEPER") (class "Default")
      (node (ref "SV4") (pin "2") (pinfunction "2_2") (pintype "passive"))
      (node (ref "U$1") (pin "41") (pinfunction "41_41") (pintype "bidirectional"))
    )
    (net (code "15") (name "CANRX") (class "Default")
      (node (ref "JP52") (pin "1") (pinfunction "1_1") (pintype "passive"))
      (node (ref "U$1") (pin "CANRX") (pinfunction "CANRX_CANRX") (pintype "bidirectional"))
    )
    (net (code "16") (name "CANTX") (class "Default")
      (node (ref "JP26") (pin "1") (pinfunction "1_1") (pintype "passive"))
      (node (ref "U$1") (pin "CANTX") (pinfunction "CANTX_CANTX") (pintype "bidirectional"))
    )
    (net (code "17") (name "CARDDETECT") (class "Default")
      (node (ref "SV5") (pin "8") (pinfunction "8_8") (pintype "passive"))
      (node (ref "U$1") (pin "TX3") (pinfunction "TX3_TX3") (pintype "bidirectional"))
    )
    (net (code "18") (name "CS0") (class "Default")
      (node (ref "JP21") (pin "1") (pinfunction "1_1") (pintype "passive"))
      (node (ref "U$1") (pin "10") (pinfunction "10_10") (pintype "bidirectional"))
    )
    (net (code "19") (name "CS1") (class "Default")
      (node (ref "SV5") (pin "3") (pinfunction "3_3") (pintype "passive"))
      (node (ref "U$1") (pin "4") (pinfunction "4_4") (pintype "bidirectional"))
    )
    (net (code "20") (name "DAC0") (class "Default")
      (node (ref "JP53") (pin "1") (pinfunction "1_1") (pintype "passive"))
      (node (ref "U$1") (pin "DAC0") (pinfunction "DAC0_DAC0") (pintype "bidirectional"))
    )
    (net (code "21") (name "DAC1") (class "Default")
      (node (ref "JP54") (pin "1") (pinfunction "1_1") (pintype "passive"))
      (node (ref "U$1") (pin "DAC1") (pinfunction "DAC1_DAC1") (pintype "bidirectional"))
    )
    (net (code "22") (name "E-DIR") (class "Default")
      (node (ref "STEPSTICK-Z2") (pin "DIR") (pinfunction "DIR_DIR") (pintype "bidirectional"))
      (node (ref "U$1") (pin "A6") (pinfunction "A6_A6") (pintype "bidirectional"))
    )
    (net (code "23") (name "E-ENA") (class "Default")
      (node (ref "R7") (pin "2") (pinfunction "2_2") (pintype "passive"))
      (node (ref "STEPSTICK-Z2") (pin "ENABLE") (pinfunction "EN_ENABLE") (pintype "bidirectional"))
      (node (ref "U$1") (pin "A8") (pinfunction "A8_A8") (pintype "bidirectional"))
    )
    (net (code "24") (name "E-STP") (class "Default")
      (node (ref "STEPSTICK-Z2") (pin "STP") (pinfunction "STEP_STP") (pintype "bidirectional"))
      (node (ref "U$1") (pin "A7") (pinfunction "A7_A7") (pintype "bidirectional"))
    )
    (net (code "25") (name "ENCA") (class "Default")
      (node (ref "SV5") (pin "4") (pinfunction "4_4") (pintype "passive"))
      (node (ref "U$1") (pin "52") (pinfunction "52_52") (pintype "bidirectional"))
    )
    (net (code "26") (name "ENCB") (class "Default")
      (node (ref "SV5") (pin "6") (pinfunction "6_6") (pintype "passive"))
      (node (ref "U$1") (pin "50") (pinfunction "50_50") (pintype "bidirectional"))
    )
    (net (code "27") (name "ENCP") (class "Default")
      (node (ref "SV4") (pin "1") (pinfunction "1_1") (pintype "passive"))
      (node (ref "U$1") (pin "48") (pinfunction "48_48") (pintype "bidirectional"))
    )
    (net (code "28") (name "FAN1") (class "Default")
      (node (ref "R35") (pin "2") (pinfunction "2_2") (pintype "passive"))
      (node (ref "U$1") (pin "11") (pinfunction "11_11") (pintype "bidirectional"))
    )
    (net (code "29") (name "FAN2") (class "Default")
      (node (ref "R27") (pin "2") (pinfunction "2_2") (pintype "passive"))
      (node (ref "U$1") (pin "12") (pinfunction "12_12") (pintype "bidirectional"))
    )
    (net (code "30") (name "FAN3") (class "Default")
      (node (ref "R40") (pin "2") (pinfunction "2_2") (pintype "passive"))
      (node (ref "U$1") (pin "9") (pinfunction "9_9") (pintype "bidirectional"))
    )
    (net (code "31") (name "GND") (class "Default")
      (node (ref "C1") (pin "2") (pinfunction "2_2") (pintype "passive"))
      (node (ref "C10") (pin "-") (pinfunction "-_-") (pintype "passive"))
      (node (ref "C11") (pin "2") (pinfunction "2_2") (pintype "passive"))
      (node (ref "C12") (pin "2") (pinfunction "2_2") (pintype "passive"))
      (node (ref "C13") (pin "2") (pinfunction "2_2") (pintype "passive"))
      (node (ref "C14") (pin "2") (pinfunction "2_2") (pintype "passive"))
      (node (ref "C16") (pin "2") (pinfunction "2_2") (pintype "passive"))
      (node (ref "C17") (pin "2") (pinfunction "2_2") (pintype "passive"))
      (node (ref "C19") (pin "2") (pinfunction "2_2") (pintype "passive"))
      (node (ref "C2") (pin "2") (pinfunction "2_2") (pintype "passive"))
      (node (ref "C21") (pin "2") (pinfunction "2_2") (pintype "passive"))
      (node (ref "C3") (pin "-") (pinfunction "-_-") (pintype "passive"))
      (node (ref "C32") (pin "1") (pinfunction "1_1") (pintype "passive"))
      (node (ref "C4") (pin "2") (pinfunction "2_2") (pintype "passive"))
      (node (ref "C46") (pin "1") (pinfunction "1_1") (pintype "passive"))
      (node (ref "C47") (pin "1") (pinfunction "1_1") (pintype "passive"))
      (node (ref "C49") (pin "1") (pinfunction "1_1") (pintype "passive"))
      (node (ref "C5") (pin "2") (pinfunction "2_2") (pintype "passive"))
      (node (ref "C51") (pin "1") (pinfunction "1_1") (pintype "passive"))
      (node (ref "C57") (pin "2") (pinfunction "2_2") (pintype "passive"))
      (node (ref "C59") (pin "2") (pinfunction "2_2") (pintype "passive"))
      (node (ref "C6") (pin "-") (pinfunction "-_-") (pintype "passive"))
      (node (ref "C61") (pin "2") (pinfunction "2_2") (pintype "passive"))
      (node (ref "C65") (pin "-") (pinfunction "-_-") (pintype "passive"))
      (node (ref "C67") (pin "-") (pinfunction "-_-") (pintype "passive"))
      (node (ref "C7") (pin "2") (pinfunction "2_2") (pintype "passive"))
      (node (ref "C8") (pin "-") (pinfunction "-_-") (pintype "passive"))
      (node (ref "C9") (pin "2") (pinfunction "2_2") (pintype "passive"))
      (node (ref "D4") (pin "A") (pinfunction "A_A") (pintype "passive"))
      (node (ref "FET1") (pin "S") (pinfunction "S_S") (pintype "bidirectional"))
      (node (ref "FET2") (pin "S") (pinfunction "S_S") (pintype "bidirectional"))
      (node (ref "H16") (pin "2") (pinfunction "2_2") (pintype "passive"))
      (node (ref "H17") (pin "2") (pinfunction "2_2") (pintype "passive"))
      (node (ref "H18") (pin "2") (pinfunction "2_2") (pintype "passive"))
      (node (ref "H19") (pin "2") (pinfunction "2_2") (pintype "passive"))
      (node (ref "H21") (pin "1") (pinfunction "1_1") (pintype "passive"))
      (node (ref "IC2") (pin "1") (pinfunction "A0_1") (pintype "input"))
      (node (ref "IC2") (pin "2") (pinfunction "A1_2") (pintype "input"))
      (node (ref "IC2") (pin "3") (pinfunction "A2_3") (pintype "input"))
      (node (ref "IC2") (pin "4") (pinfunction "GND_4") (pintype "power_in"))
      (node (ref "IC2") (pin "7") (pinfunction "WP_7") (pintype "input"))
      (node (ref "IC5") (pin "3") (pinfunction "GND_3") (pintype "power_in"))
      (node (ref "IC5") (pin "5") (pinfunction "~{ON}/OFF_5") (pintype "input"))
      (node (ref "JP1") (pin "1") (pinfunction "1_1") (pintype "passive"))
      (node (ref "JP10") (pin "1") (pinfunction "1_1") (pintype "passive"))
      (node (ref "JP12") (pin "1") (pinfunction "1_1") (pintype "passive"))
      (node (ref "JP33") (pin "1") (pinfunction "1_1") (pintype "passive"))
      (node (ref "JP34") (pin "1") (pinfunction "1_1") (pintype "passive"))
      (node (ref "JP37") (pin "1") (pinfunction "1_1") (pintype "passive"))
      (node (ref "JP39") (pin "1") (pinfunction "1_1") (pintype "passive"))
      (node (ref "JP8") (pin "1") (pinfunction "1_1") (pintype "passive"))
      (node (ref "LED5") (pin "C") (pinfunction "C_C") (pintype "passive"))
      (node (ref "LED6") (pin "C") (pinfunction "C_C") (pintype "passive"))
      (node (ref "LED7") (pin "C") (pinfunction "C_C") (pintype "passive"))
      (node (ref "P2") (pin "2") (pinfunction "2_2") (pintype "passive"))
      (node (ref "P5") (pin "2") (pinfunction "2_2") (pintype "passive"))
      (node (ref "P7") (pin "2") (pinfunction "2_2") (pintype "passive"))
      (node (ref "Q1") (pin "2") (pinfunction "S_2") (pintype "passive"))
      (node (ref "Q2") (pin "2") (pinfunction "S_2") (pintype "passive"))
      (node (ref "Q3") (pin "2") (pinfunction "S_2") (pintype "passive"))
      (node (ref "R2") (pin "1") (pinfunction "1_1") (pintype "passive"))
      (node (ref "R22") (pin "1") (pinfunction "1_1") (pintype "passive"))
      (node (ref "R36") (pin "2") (pinfunction "2_2") (pintype "passive"))
      (node (ref "R37") (pin "2") (pinfunction "2_2") (pintype "passive"))
      (node (ref "R4") (pin "1") (pinfunction "1_1") (pintype "passive"))
      (node (ref "R41") (pin "2") (pinfunction "2_2") (pintype "passive"))
      (node (ref "R48") (pin "2") (pinfunction "2_2") (pintype "passive"))
      (node (ref "R51") (pin "2") (pinfunction "2_2") (pintype "passive"))
      (node (ref "R6") (pin "1") (pinfunction "1_1") (pintype "passive"))
      (node (ref "R8") (pin "1") (pinfunction "1_1") (pintype "passive"))
      (node (ref "RESET") (pin "2") (pinfunction "2_2") (pintype "bidirectional"))
      (node (ref "STEPSTICK-X") (pin "GND") (pinfunction "GNDM_GND") (pintype "bidirectional"))
      (node (ref "STEPSTICK-X") (pin "GND1") (pinfunction "GND_GND1") (pintype "bidirectional"))
      (node (ref "STEPSTICK-Y") (pin "GND") (pinfunction "GNDM_GND") (pintype "bidirectional"))
      (node (ref "STEPSTICK-Y") (pin "GND1") (pinfunction "GND_GND1") (pintype "bidirectional"))
      (node (ref "STEPSTICK-Z1") (pin "GND") (pinfunction "GNDM_GND") (pintype "bidirectional"))
      (node (ref "STEPSTICK-Z1") (pin "GND1") (pinfunction "GND_GND1") (pintype "bidirectional"))
      (node (ref "STEPSTICK-Z2") (pin "GND") (pinfunction "GNDM_GND") (pintype "bidirectional"))
      (node (ref "STEPSTICK-Z2") (pin "GND1") (pinfunction "GND_GND1") (pintype "bidirectional"))
      (node (ref "SV4") (pin "10") (pinfunction "10_10") (pintype "passive"))
      (node (ref "SV5") (pin "10") (pinfunction "10_10") (pintype "passive"))
      (node (ref "U$1") (pin "5V_ICSP") (pinfunction "5V_ICSP_5V_ICSP") (pintype "bidirectional"))
      (node (ref "U$1") (pin "GND_1") (pinfunction "GND_1_GND_1") (pintype "bidirectional"))
      (node (ref "U$1") (pin "GND_2") (pinfunction "GND_2_GND_2") (pintype "bidirectional"))
      (node (ref "U$1") (pin "GND_A") (pinfunction "GND_A_GND_A") (pintype "bidirectional"))
      (node (ref "U$1") (pin "GND_B") (pinfunction "GND_B_GND_B") (pintype "bidirectional"))
    )
    (net (code "32") (name "HOT1") (class "Default")
      (node (ref "R50") (pin "2") (pinfunction "2_2") (pintype "passive"))
      (node (ref "R52") (pin "1") (pinfunction "1_1") (pintype "passive"))
      (node (ref "U$1") (pin "13") (pinfunction "13_13") (pintype "bidirectional"))
    )
    (net (code "33") (name "LCD4") (class "Default")
      (node (ref "SV4") (pin "6") (pinfunction "6_6") (pintype "passive"))
      (node (ref "U$1") (pin "44") (pinfunction "44_44") (pintype "bidirectional"))
    )
    (net (code "34") (name "LCD5") (class "Default")
      (node (ref "SV4") (pin "5") (pinfunction "5_5") (pintype "passive"))
      (node (ref "U$1") (pin "45") (pinfunction "45_45") (pintype "bidirectional"))
    )
    (net (code "35") (name "LCD6") (class "Default")
      (node (ref "SV4") (pin "8") (pinfunction "8_8") (pintype "passive"))
      (node (ref "U$1") (pin "46") (pinfunction "46_46") (pintype "bidirectional"))
    )
    (net (code "36") (name "LCD7") (class "Default")
      (node (ref "SV4") (pin "7") (pinfunction "7_7") (pintype "passive"))
      (node (ref "U$1") (pin "47") (pinfunction "47_47") (pintype "bidirectional"))
    )
    (net (code "37") (name "LCD_ENA") (class "Default")
      (node (ref "SV4") (pin "4") (pinfunction "4_4") (pintype "passive"))
      (node (ref "U$1") (pin "43") (pinfunction "43_43") (pintype "bidirectional"))
    )
    (net (code "38") (name "LCD_RS") (class "Default")
      (node (ref "SV4") (pin "3") (pinfunction "3_3") (pintype "passive"))
      (node (ref "U$1") (pin "42") (pinfunction "42_42") (pintype "bidirectional"))
    )
    (net (code "39") (name "MISO") (class "Default")
      (node (ref "JP1") (pin "6") (pinfunction "6_6") (pintype "passive"))
      (node (ref "SV5") (pin "2") (pinfunction "2_2") (pintype "passive"))
      (node (ref "U$1") (pin "MISO_ICSP") (pinfunction "MISO_ICSP_MISO_ICSP") (pintype "bidirectional"))
    )
    (net (code "40") (name "MOSI") (class "Default")
      (node (ref "JP1") (pin "3") (pinfunction "3_3") (pintype "passive"))
      (node (ref "SV5") (pin "5") (pinfunction "5_5") (pintype "passive"))
      (node (ref "U$1") (pin "MOSI_ICSP") (pinfunction "MOSI_ICSP_MOSI_ICSP") (pintype "bidirectional"))
    )
    (net (code "41") (name "NTC1") (class "Default")
      (node (ref "R24") (pin "2") (pinfunction "2_2") (pintype "passive"))
      (node (ref "U$1") (pin "A0") (pinfunction "A0_A0") (pintype "bidirectional"))
    )
    (net (code "42") (name "NTC2") (class "Default")
      (node (ref "R32") (pin "2") (pinfunction "2_2") (pintype "passive"))
      (node (ref "U$1") (pin "A1") (pinfunction "A1_A1") (pintype "bidirectional"))
    )
    (net (code "43") (name "NTC3") (class "Default")
      (node (ref "R33") (pin "2") (pinfunction "2_2") (pintype "passive"))
      (node (ref "U$1") (pin "A2") (pinfunction "A2_A2") (pintype "bidirectional"))
    )
    (net (code "44") (name "Net-(C3-Pad+)") (class "Default")
      (node (ref "C3") (pin "+") (pinfunction "+_+") (pintype "passive"))
      (node (ref "C4") (pin "1") (pinfunction "1_1") (pintype "passive"))
      (node (ref "L2") (pin "1") (pinfunction "1_1") (pintype "passive"))
      (node (ref "STEPSTICK-X") (pin "VMOT") (pinfunction "VMOT_VMOT") (pintype "bidirectional"))
    )
    (net (code "45") (name "Net-(C6-Pad+)") (class "Default")
      (node (ref "C6") (pin "+") (pinfunction "+_+") (pintype "passive"))
      (node (ref "C9") (pin "1") (pinfunction "1_1") (pintype "passive"))
      (node (ref "L4") (pin "1") (pinfunction "1_1") (pintype "passive"))
      (node (ref "STEPSTICK-Y") (pin "VMOT") (pinfunction "VMOT_VMOT") (pintype "bidirectional"))
    )
    (net (code "46") (name "Net-(C10-Pad+)") (class "Default")
      (node (ref "C10") (pin "+") (pinfunction "+_+") (pintype "passive"))
      (node (ref "C19") (pin "1") (pinfunction "1_1") (pintype "passive"))
      (node (ref "L8") (pin "1") (pinfunction "1_1") (pintype "passive"))
      (node (ref "STEPSTICK-Z2") (pin "VMOT") (pinfunction "VMOT_VMOT") (pintype "bidirectional"))
    )
    (net (code "47") (name "Net-(C14-Pad1)") (class "Default")
      (node (ref "C14") (pin "1") (pinfunction "1_1") (pintype "passive"))
      (node (ref "C8") (pin "+") (pinfunction "+_+") (pintype "passive"))
      (node (ref "L6") (pin "1") (pinfunction "1_1") (pintype "passive"))
      (node (ref "STEPSTICK-Z1") (pin "VMOT") (pinfunction "VMOT_VMOT") (pintype "bidirectional"))
    )
    (net (code "48") (name "Net-(C57-Pad1)") (class "Default")
      (node (ref "C57") (pin "1") (pinfunction "1_1") (pintype "passive"))
      (node (ref "H17") (pin "1") (pinfunction "1_1") (pintype "passive"))
      (node (ref "R24") (pin "1") (pinfunction "1_1") (pintype "passive"))
      (node (ref "R28") (pin "1") (pinfunction "1_1") (pintype "passive"))
    )
    (net (code "49") (name "Net-(C59-Pad1)") (class "Default")
      (node (ref "C59") (pin "1") (pinfunction "1_1") (pintype "passive"))
      (node (ref "H18") (pin "1") (pinfunction "1_1") (pintype "passive"))
      (node (ref "R29") (pin "1") (pinfunction "1_1") (pintype "passive"))
      (node (ref "R32") (pin "1") (pinfunction "1_1") (pintype "passive"))
    )
    (net (code "50") (name "Net-(C61-Pad1)") (class "Default")
      (node (ref "C61") (pin "1") (pinfunction "1_1") (pintype "passive"))
      (node (ref "H19") (pin "1") (pinfunction "1_1") (pintype "passive"))
      (node (ref "R30") (pin "1") (pinfunction "1_1") (pintype "passive"))
      (node (ref "R33") (pin "1") (pinfunction "1_1") (pintype "passive"))
    )
    (net (code "51") (name "Net-(C67-Pad+)") (class "Default")
      (node (ref "C67") (pin "+") (pinfunction "+_+") (pintype "passive"))
      (node (ref "C68") (pin "2") (pinfunction "2_2") (pintype "passive"))
      (node (ref "L17") (pin "1") (pinfunction "1_1") (pintype "passive"))
      (node (ref "L19") (pin "2") (pinfunction "2_2") (pintype "passive"))
      (node (ref "R23") (pin "2") (pinfunction "2_2") (pintype "passive"))
    )
    (net (code "52") (name "Net-(D1-PadC)") (class "Default")
      (node (ref "D1") (pin "C") (pinfunction "C_C") (pintype "passive"))
      (node (ref "U$1") (pin "VIN") (pinfunction "VIN_VIN") (pintype "bidirectional"))
    )
    (net (code "53") (name "Net-(D3-PadA)") (class "Default")
      (node (ref "D3") (pin "A") (pinfunction "A_A") (pintype "passive"))
      (node (ref "L15") (pin "2") (pinfunction "2_2") (pintype "passive"))
    )
    (net (code "54") (name "Net-(FET1-PadD)") (class "Default")
      (node (ref "FET1") (pin "D") (pinfunction "D_D") (pintype "bidirectional"))
      (node (ref "P4") (pin "2") (pinfunction "2_2") (pintype "passive"))
    )
    (net (code "55") (name "Net-(FET1-PadG)") (class "Default")
      (node (ref "FET1") (pin "G") (pinfunction "G_G") (pintype "bidirectional"))
      (node (ref "R50") (pin "1") (pinfunction "1_1") (pintype "passive"))
      (node (ref "R51") (pin "1") (pinfunction "1_1") (pintype "passive"))
    )
    (net (code "56") (name "Net-(FET2-PadD)") (class "Default")
      (node (ref "FET2") (pin "D") (pinfunction "D_D") (pintype "bidirectional"))
      (node (ref "P3") (pin "2") (pinfunction "2_2") (pintype "passive"))
    )
    (net (code "57") (name "Net-(FET2-PadG)") (class "Default")
      (node (ref "FET2") (pin "G") (pinfunction "G_G") (pintype "bidirectional"))
      (node (ref "R47") (pin "1") (pinfunction "1_1") (pintype "passive"))
      (node (ref "R48") (pin "1") (pinfunction "1_1") (pintype "passive"))
    )
    (net (code "58") (name "Net-(FUSE-1-PadP$1)") (class "Default")
      (node (ref "FUSE") (pin "P$1") (pinfunction "1_P$1") (pintype "bidirectional"))
      (node (ref "FUSE") (pin "P$2") (pinfunction "1_P$2") (pintype "bidirectional"))
      (node (ref "P2") (pin "1") (pinfunction "1_1") (pintype "passive"))
    )
    (net (code "59") (name "Net-(FUSE-2-PadP$3)") (class "Default")
      (node (ref "FUSE") (pin "P$3") (pinfunction "2_P$3") (pintype "bidirectional"))
      (node (ref "FUSE") (pin "P$4") (pinfunction "2_P$4") (pintype "bidirectional"))
      (node (ref "P3") (pin "1") (pinfunction "1_1") (pintype "passive"))
    )
    (net (code "60") (name "Net-(IC5-FB)") (class "Default")
      (node (ref "C68") (pin "1") (pinfunction "1_1") (pintype "passive"))
      (node (ref "IC5") (pin "4") (pinfunction "FB_4") (pintype "input"))
      (node (ref "R22") (pin "2") (pinfunction "2_2") (pintype "passive"))
      (node (ref "R23") (pin "1") (pinfunction "1_1") (pintype "passive"))
    )
    (net (code "61") (name "Net-(IC5-OUT)") (class "Default")
      (node (ref "D4") (pin "C") (pinfunction "C_C") (pintype "passive"))
      (node (ref "IC5") (pin "2") (pinfunction "OUT_2") (pintype "output"))
      (node (ref "L19") (pin "1") (pinfunction "1_1") (pintype "passive"))
    )
    (net (code "62") (name "Net-(IC5-VIN)") (class "Default")
      (node (ref "C65") (pin "+") (pinfunction "+_+") (pintype "passive"))
      (node (ref "D3") (pin "C") (pinfunction "C_C") (pintype "passive"))
      (node (ref "IC5") (pin "1") (pinfunction "VIN_1") (pintype "input"))
      (node (ref "JP7") (pin "3") (pinfunction "3_3") (pintype "passive"))
    )
    (net (code "63") (name "Net-(J1-Pad1)") (class "Default")
      (node (ref "J1") (pin "1") (pinfunction "1_1") (pintype "passive"))
      (node (ref "STEPSTICK-X") (pin "1A") (pinfunction "1A_1A") (pintype "bidirectional"))
    )
    (net (code "64") (name "Net-(J1-Pad2)") (class "Default")
      (node (ref "J1") (pin "2") (pinfunction "2_2") (pintype "passive"))
      (node (ref "STEPSTICK-X") (pin "1B") (pinfunction "1B_1B") (pintype "bidirectional"))
    )
    (net (code "65") (name "Net-(J1-Pad3)") (class "Default")
      (node (ref "J1") (pin "3") (pinfunction "3_3") (pintype "passive"))
      (node (ref "STEPSTICK-X") (pin "2A") (pinfunction "2A_2A") (pintype "bidirectional"))
    )
    (net (code "66") (name "Net-(J1-Pad4)") (class "Default")
      (node (ref "J1") (pin "4") (pinfunction "4_4") (pintype "passive"))
      (node (ref "STEPSTICK-X") (pin "2B") (pinfunction "2B_2B") (pintype "bidirectional"))
    )
    (net (code "67") (name "Net-(J2-Pad1)") (class "Default")
      (node (ref "J2") (pin "1") (pinfunction "1_1") (pintype "passive"))
      (node (ref "STEPSTICK-Y") (pin "1A") (pinfunction "1A_1A") (pintype "bidirectional"))
    )
    (net (code "68") (name "Net-(J2-Pad2)") (class "Default")
      (node (ref "J2") (pin "2") (pinfunction "2_2") (pintype "passive"))
      (node (ref "STEPSTICK-Y") (pin "1B") (pinfunction "1B_1B") (pintype "bidirectional"))
    )
    (net (code "69") (name "Net-(J2-Pad3)") (class "Default")
      (node (ref "J2") (pin "3") (pinfunction "3_3") (pintype "passive"))
      (node (ref "STEPSTICK-Y") (pin "2A") (pinfunction "2A_2A") (pintype "bidirectional"))
    )
    (net (code "70") (name "Net-(J2-Pad4)") (class "Default")
      (node (ref "J2") (pin "4") (pinfunction "4_4") (pintype "passive"))
      (node (ref "STEPSTICK-Y") (pin "2B") (pinfunction "2B_2B") (pintype "bidirectional"))
    )
    (net (code "71") (name "Net-(J3-Pad1)") (class "Default")
      (node (ref "J3") (pin "1") (pinfunction "1_1") (pintype "passive"))
      (node (ref "STEPSTICK-Z1") (pin "1A") (pinfunction "1A_1A") (pintype "bidirectional"))
    )
    (net (code "72") (name "Net-(J3-Pad2)") (class "Default")
      (node (ref "J3") (pin "2") (pinfunction "2_2") (pintype "passive"))
      (node (ref "STEPSTICK-Z1") (pin "1B") (pinfunction "1B_1B") (pintype "bidirectional"))
    )
    (net (code "73") (name "Net-(J3-Pad3)") (class "Default")
      (node (ref "J3") (pin "3") (pinfunction "3_3") (pintype "passive"))
      (node (ref "STEPSTICK-Z1") (pin "2A") (pinfunction "2A_2A") (pintype "bidirectional"))
    )
    (net (code "74") (name "Net-(J3-Pad4)") (class "Default")
      (node (ref "J3") (pin "4") (pinfunction "4_4") (pintype "passive"))
      (node (ref "STEPSTICK-Z1") (pin "2B") (pinfunction "2B_2B") (pintype "bidirectional"))
    )
    (net (code "75") (name "Net-(J4-Pad1)") (class "Default")
      (node (ref "J4") (pin "1") (pinfunction "1_1") (pintype "passive"))
      (node (ref "STEPSTICK-Z2") (pin "1A") (pinfunction "1A_1A") (pintype "bidirectional"))
    )
    (net (code "76") (name "Net-(J4-Pad2)") (class "Default")
      (node (ref "J4") (pin "2") (pinfunction "2_2") (pintype "passive"))
      (node (ref "STEPSTICK-Z2") (pin "1B") (pinfunction "1B_1B") (pintype "bidirectional"))
    )
    (net (code "77") (name "Net-(J4-Pad3)") (class "Default")
      (node (ref "J4") (pin "3") (pinfunction "3_3") (pintype "passive"))
      (node (ref "STEPSTICK-Z2") (pin "2A") (pinfunction "2A_2A") (pintype "bidirectional"))
    )
    (net (code "78") (name "Net-(J4-Pad4)") (class "Default")
      (node (ref "J4") (pin "4") (pinfunction "4_4") (pintype "passive"))
      (node (ref "STEPSTICK-Z2") (pin "2B") (pinfunction "2B_2B") (pintype "bidirectional"))
    )
    (net (code "79") (name "Net-(JP8-Pad3)") (class "Default")
      (node (ref "JP8") (pin "3") (pinfunction "3_3") (pintype "passive"))
      (node (ref "R16") (pin "2") (pinfunction "2_2") (pintype "passive"))
    )
    (net (code "80") (name "Net-(JP10-Pad3)") (class "Default")
      (node (ref "JP10") (pin "3") (pinfunction "3_3") (pintype "passive"))
      (node (ref "R18") (pin "2") (pinfunction "2_2") (pintype "passive"))
    )
    (net (code "81") (name "Net-(JP12-Pad3)") (class "Default")
      (node (ref "JP12") (pin "3") (pinfunction "3_3") (pintype "passive"))
      (node (ref "R20") (pin "2") (pinfunction "2_2") (pintype "passive"))
    )
    (net (code "82") (name "Net-(JP62-Pad1)") (class "Default")
      (node (ref "JP62") (pin "1") (pinfunction "1_1") (pintype "passive"))
      (node (ref "U$1") (pin "28") (pinfunction "28_28") (pintype "bidirectional"))
    )
    (net (code "83") (name "Net-(JP63-Pad1)") (class "Default")
      (node (ref "JP63") (pin "1") (pinfunction "1_1") (pintype "passive"))
      (node (ref "U$1") (pin "32") (pinfunction "32_32") (pintype "bidirectional"))
    )
    (net (code "84") (name "Net-(JP64-Pad1)") (class "Default")
      (node (ref "JP64") (pin "1") (pinfunction "1_1") (pintype "passive"))
      (node (ref "U$1") (pin "36") (pinfunction "36_36") (pintype "bidirectional"))
    )
    (net (code "85") (name "Net-(JP65-Pad1)") (class "Default")
      (node (ref "JP65") (pin "1") (pinfunction "1_1") (pintype "passive"))
      (node (ref "U$1") (pin "39") (pinfunction "39_39") (pintype "bidirectional"))
    )
    (net (code "86") (name "Net-(JP66-Pad1)") (class "Default")
      (node (ref "JP66") (pin "1") (pinfunction "1_1") (pintype "passive"))
      (node (ref "U$1") (pin "49") (pinfunction "49_49") (pintype "bidirectional"))
    )
    (net (code "87") (name "Net-(JP67-Pad1)") (class "Default")
      (node (ref "JP67") (pin "1") (pinfunction "1_1") (pintype "passive"))
      (node (ref "U$1") (pin "51") (pinfunction "51_51") (pintype "bidirectional"))
    )
    (net (code "88") (name "Net-(JP68-Pad1)") (class "Default")
      (node (ref "JP68") (pin "1") (pinfunction "1_1") (pintype "passive"))
      (node (ref "U$1") (pin "53") (pinfunction "53_53") (pintype "bidirectional"))
    )
    (net (code "89") (name "Net-(JP69-Pad1)") (class "Default")
      (node (ref "JP69") (pin "1") (pinfunction "1_1") (pintype "passive"))
      (node (ref "U$1") (pin "A3") (pinfunction "A3_A3") (pintype "bidirectional"))
    )
    (net (code "90") (name "Net-(JP70-Pad1)") (class "Default")
      (node (ref "JP70") (pin "1") (pinfunction "1_1") (pintype "passive"))
      (node (ref "U$1") (pin "A4") (pinfunction "A4_A4") (pintype "bidirectional"))
    )
    (net (code "91") (name "Net-(JP71-Pad1)") (class "Default")
      (node (ref "JP71") (pin "1") (pinfunction "1_1") (pintype "passive"))
      (node (ref "U$1") (pin "A11") (pinfunction "A11_A11") (pintype "bidirectional"))
    )
    (net (code "92") (name "Net-(JP72-Pad1)") (class "Default")
      (node (ref "JP72") (pin "1") (pinfunction "1_1") (pintype "passive"))
      (node (ref "U$1") (pin "23") (pinfunction "23_23") (pintype "bidirectional"))
    )
    (net (code "93") (name "Net-(JP73-Pad1)") (class "Default")
      (node (ref "JP73") (pin "1") (pinfunction "1_1") (pintype "passive"))
      (node (ref "U$1") (pin "24") (pinfunction "24_24") (pintype "bidirectional"))
    )
    (net (code "94") (name "Net-(LED1-PadA)") (class "Default")
      (node (ref "LED1") (pin "A") (pinfunction "A_A") (pintype "passive"))
      (node (ref "R26") (pin "2") (pinfunction "2_2") (pintype "passive"))
    )
    (net (code "95") (name "Net-(LED2-PadA)") (class "Default")
      (node (ref "LED2") (pin "A") (pinfunction "A_A") (pintype "passive"))
      (node (ref "R38") (pin "2") (pinfunction "2_2") (pintype "passive"))
    )
    (net (code "96") (name "Net-(LED3-PadA)") (class "Default")
      (node (ref "LED3") (pin "A") (pinfunction "A_A") (pintype "passive"))
      (node (ref "R43") (pin "2") (pinfunction "2_2") (pintype "passive"))
    )
    (net (code "97") (name "Net-(LED5-PadA)") (class "Default")
      (node (ref "LED5") (pin "A") (pinfunction "A_A") (pintype "passive"))
      (node (ref "R49") (pin "1") (pinfunction "1_1") (pintype "passive"))
    )
    (net (code "98") (name "Net-(LED6-PadA)") (class "Default")
      (node (ref "LED6") (pin "A") (pinfunction "A_A") (pintype "passive"))
      (node (ref "R52") (pin "2") (pinfunction "2_2") (pintype "passive"))
    )
    (net (code "99") (name "Net-(LED7-PadA)") (class "Default")
      (node (ref "LED7") (pin "A") (pinfunction "A_A") (pintype "passive"))
      (node (ref "R39") (pin "1") (pinfunction "1_1") (pintype "passive"))
    )
    (net (code "100") (name "Net-(P4-Pad1)") (class "Default")
      (node (ref "P4") (pin "1") (pinfunction "1_1") (pintype "passive"))
      (node (ref "U$2") (pin "1") (pinfunction "1_1") (pintype "bidirectional"))
    )
    (net (code "101") (name "Net-(P5-Pad1)") (class "Default")
      (node (ref "P5") (pin "1") (pinfunction "1_1") (pintype "passive"))
      (node (ref "U$2") (pin "2") (pinfunction "2_2") (pintype "bidirectional"))
    )
    (net (code "102") (name "Net-(P7-Pad1)") (class "Default")
      (node (ref "P7") (pin "1") (pinfunction "1_1") (pintype "passive"))
      (node (ref "U$3") (pin "2") (pinfunction "2_2") (pintype "bidirectional"))
    )
    (net (code "103") (name "Net-(Q1-D)") (class "Default")
      (node (ref "H13") (pin "2") (pinfunction "2_2") (pintype "passive"))
      (node (ref "LED1") (pin "C") (pinfunction "C_C") (pintype "passive"))
      (node (ref "Q1") (pin "3") (pinfunction "D_3") (pintype "passive"))
    )
    (net (code "104") (name "Net-(Q1-G)") (class "Default")
      (node (ref "Q1") (pin "1") (pinfunction "G_1") (pintype "passive"))
      (node (ref "R35") (pin "1") (pinfunction "1_1") (pintype "passive"))
      (node (ref "R36") (pin "1") (pinfunction "1_1") (pintype "passive"))
    )
    (net (code "105") (name "Net-(Q2-D)") (class "Default")
      (node (ref "H14") (pin "2") (pinfunction "2_2") (pintype "passive"))
      (node (ref "LED2") (pin "C") (pinfunction "C_C") (pintype "passive"))
      (node (ref "Q2") (pin "3") (pinfunction "D_3") (pintype "passive"))
    )
    (net (code "106") (name "Net-(Q2-G)") (class "Default")
      (node (ref "Q2") (pin "1") (pinfunction "G_1") (pintype "passive"))
      (node (ref "R27") (pin "1") (pinfunction "1_1") (pintype "passive"))
      (node (ref "R37") (pin "1") (pinfunction "1_1") (pintype "passive"))
    )
    (net (code "107") (name "Net-(Q3-D)") (class "Default")
      (node (ref "H15") (pin "2") (pinfunction "2_2") (pintype "passive"))
      (node (ref "LED3") (pin "C") (pinfunction "C_C") (pintype "passive"))
      (node (ref "Q3") (pin "3") (pinfunction "D_3") (pintype "passive"))
    )
    (net (code "108") (name "Net-(Q3-G)") (class "Default")
      (node (ref "Q3") (pin "1") (pinfunction "G_1") (pintype "passive"))
      (node (ref "R40") (pin "1") (pinfunction "1_1") (pintype "passive"))
      (node (ref "R41") (pin "1") (pinfunction "1_1") (pintype "passive"))
    )
    (net (code "109") (name "Net-(R2-Pad2)") (class "Default")
      (node (ref "R2") (pin "2") (pinfunction "2_2") (pintype "passive"))
      (node (ref "SJ1") (pin "2") (pinfunction "2_2") (pintype "passive"))
      (node (ref "STEPSTICK-X") (pin "MS1") (pinfunction "MS1_MS1") (pintype "bidirectional"))
    )
    (net (code "110") (name "Net-(R4-Pad2)") (class "Default")
      (node (ref "R4") (pin "2") (pinfunction "2_2") (pintype "passive"))
      (node (ref "SJ4") (pin "2") (pinfunction "2_2") (pintype "passive"))
      (node (ref "STEPSTICK-Y") (pin "MS1") (pinfunction "MS1_MS1") (pintype "bidirectional"))
    )
    (net (code "111") (name "Net-(R6-Pad2)") (class "Default")
      (node (ref "R6") (pin "2") (pinfunction "2_2") (pintype "passive"))
      (node (ref "SJ7") (pin "2") (pinfunction "2_2") (pintype "passive"))
      (node (ref "STEPSTICK-Z1") (pin "MS1") (pinfunction "MS1_MS1") (pintype "bidirectional"))
    )
    (net (code "112") (name "Net-(R8-Pad2)") (class "Default")
      (node (ref "R8") (pin "2") (pinfunction "2_2") (pintype "passive"))
      (node (ref "SJ10") (pin "2") (pinfunction "2_2") (pintype "passive"))
      (node (ref "STEPSTICK-Z2") (pin "MS1") (pinfunction "MS1_MS1") (pintype "bidirectional"))
    )
    (net (code "113") (name "Net-(SJ2-Pad2)") (class "Default")
      (node (ref "SJ2") (pin "2") (pinfunction "2_2") (pintype "passive"))
      (node (ref "STEPSTICK-X") (pin "MS2") (pinfunction "MS2_MS2") (pintype "bidirectional"))
    )
    (net (code "114") (name "Net-(SJ3-Pad2)") (class "Default")
      (node (ref "SJ3") (pin "2") (pinfunction "2_2") (pintype "passive"))
      (node (ref "STEPSTICK-X") (pin "MS3") (pinfunction "MS3_MS3") (pintype "bidirectional"))
    )
    (net (code "115") (name "Net-(SJ5-Pad2)") (class "Default")
      (node (ref "SJ5") (pin "2") (pinfunction "2_2") (pintype "passive"))
      (node (ref "STEPSTICK-Y") (pin "MS2") (pinfunction "MS2_MS2") (pintype "bidirectional"))
    )
    (net (code "116") (name "Net-(SJ6-Pad2)") (class "Default")
      (node (ref "SJ6") (pin "2") (pinfunction "2_2") (pintype "passive"))
      (node (ref "STEPSTICK-Y") (pin "MS3") (pinfunction "MS3_MS3") (pintype "bidirectional"))
    )
    (net (code "117") (name "Net-(SJ8-Pad2)") (class "Default")
      (node (ref "SJ8") (pin "2") (pinfunction "2_2") (pintype "passive"))
      (node (ref "STEPSTICK-Z1") (pin "MS2") (pinfunction "MS2_MS2") (pintype "bidirectional"))
    )
    (net (code "118") (name "Net-(SJ9-Pad2)") (class "Default")
      (node (ref "SJ9") (pin "2") (pinfunction "2_2") (pintype "passive"))
      (node (ref "STEPSTICK-Z1") (pin "MS3") (pinfunction "MS3_MS3") (pintype "bidirectional"))
    )
    (net (code "119") (name "Net-(SJ11-Pad2)") (class "Default")
      (node (ref "SJ11") (pin "2") (pinfunction "2_2") (pintype "passive"))
      (node (ref "STEPSTICK-Z2") (pin "MS2") (pinfunction "MS2_MS2") (pintype "bidirectional"))
    )
    (net (code "120") (name "Net-(SJ12-Pad2)") (class "Default")
      (node (ref "SJ12") (pin "2") (pinfunction "2_2") (pintype "passive"))
      (node (ref "STEPSTICK-Z2") (pin "MS3") (pinfunction "MS3_MS3") (pintype "bidirectional"))
    )
    (net (code "121") (name "Net-(STEPSTICK-X-RST)") (class "Default")
      (node (ref "STEPSTICK-X") (pin "RESET") (pinfunction "RST_RESET") (pintype "bidirectional"))
      (node (ref "STEPSTICK-X") (pin "SLEEP") (pinfunction "SLP_SLEEP") (pintype "bidirectional"))
    )
    (net (code "122") (name "Net-(STEPSTICK-Y-RST)") (class "Default")
      (node (ref "STEPSTICK-Y") (pin "RESET") (pinfunction "RST_RESET") (pintype "bidirectional"))
      (node (ref "STEPSTICK-Y") (pin "SLEEP") (pinfunction "SLP_SLEEP") (pintype "bidirectional"))
    )
    (net (code "123") (name "Net-(STEPSTICK-Z1-RST)") (class "Default")
      (node (ref "STEPSTICK-Z1") (pin "RESET") (pinfunction "RST_RESET") (pintype "bidirectional"))
      (node (ref "STEPSTICK-Z1") (pin "SLEEP") (pinfunction "SLP_SLEEP") (pintype "bidirectional"))
    )
    (net (code "124") (name "Net-(STEPSTICK-Z2-RST)") (class "Default")
      (node (ref "STEPSTICK-Z2") (pin "RESET") (pinfunction "RST_RESET") (pintype "bidirectional"))
      (node (ref "STEPSTICK-Z2") (pin "SLEEP") (pinfunction "SLP_SLEEP") (pintype "bidirectional"))
    )
    (net (code "125") (name "PSON") (class "Default")
      (node (ref "JP27") (pin "1") (pinfunction "1_1") (pintype "passive"))
      (node (ref "U$1") (pin "40") (pinfunction "40_40") (pintype "bidirectional"))
    )
    (net (code "126") (name "PWM1") (class "Default")
      (node (ref "JP25") (pin "1") (pinfunction "1_1") (pintype "passive"))
      (node (ref "U$1") (pin "5") (pinfunction "5_5") (pintype "bidirectional"))
    )
    (net (code "127") (name "PWM2") (class "Default")
      (node (ref "JP20") (pin "1") (pinfunction "1_1") (pintype "passive"))
      (node (ref "U$1") (pin "6") (pinfunction "6_6") (pintype "bidirectional"))
    )
    (net (code "128") (name "PWM3") (class "Default")
      (node (ref "JP19") (pin "1") (pinfunction "1_1") (pintype "passive"))
    )
    (net (code "129") (name "RESET") (class "Default")
      (node (ref "C13") (pin "1") (pinfunction "1_1") (pintype "passive"))
      (node (ref "H21") (pin "2") (pinfunction "2_2") (pintype "passive"))
      (node (ref "JP1") (pin "2") (pinfunction "2_2") (pintype "passive"))
      (node (ref "RESET") (pin "1") (pinfunction "1_1") (pintype "bidirectional"))
      (node (ref "SV5") (pin "7") (pinfunction "7_7") (pintype "passive"))
      (node (ref "U$1") (pin "RESET_ICSP") (pinfunction "RESET_ICSP_RESET_ICSP") (pintype "bidirectional"))
    )
    (net (code "130") (name "RX0") (class "Default")
      (node (ref "JP16") (pin "1") (pinfunction "1_1") (pintype "passive"))
      (node (ref "U$1") (pin "RX0") (pinfunction "RX0_RX0") (pintype "bidirectional"))
    )
    (net (code "131") (name "RX1") (class "Default")
      (node (ref "U$1") (pin "RX1") (pinfunction "RX1_RX1") (pintype "bidirectional"))
    )
    (net (code "132") (name "SCK") (class "Default")
      (node (ref "JP1") (pin "4") (pinfunction "4_4") (pintype "passive"))
      (node (ref "SV5") (pin "1") (pinfunction "1_1") (pintype "passive"))
      (node (ref "U$1") (pin "SCK_ICSP") (pinfunction "SCK_ICSP_SCK_ICSP") (pintype "bidirectional"))
    )
    (net (code "133") (name "SCL") (class "Default")
      (node (ref "H16") (pin "4") (pinfunction "4_4") (pintype "passive"))
      (node (ref "IC2") (pin "6") (pinfunction "SCL_6") (pintype "input"))
      (node (ref "U$1") (pin "SCL") (pinfunction "SCL_SCL") (pintype "bidirectional"))
    )
    (net (code "134") (name "SCL1") (class "Default")
      (node (ref "JP6") (pin "1") (pinfunction "1_1") (pintype "passive"))
      (node (ref "U$1") (pin "SCL1") (pinfunction "SCL1_SCL1") (pintype "bidirectional"))
    )
    (net (code "135") (name "SDA") (class "Default")
      (node (ref "H16") (pin "3") (pinfunction "3_3") (pintype "passive"))
      (node (ref "IC2") (pin "5") (pinfunction "SDA_5") (pintype "bidirectional"))
      (node (ref "U$1") (pin "SDA") (pinfunction "SDA_SDA") (pintype "bidirectional"))
    )
    (net (code "136") (name "SDA1") (class "Default")
      (node (ref "JP14") (pin "1") (pinfunction "1_1") (pintype "passive"))
      (node (ref "U$1") (pin "SDA1") (pinfunction "SDA1_SDA1") (pintype "bidirectional"))
    )
    (net (code "137") (name "TX0") (class "Default")
      (node (ref "JP15") (pin "1") (pinfunction "1_1") (pintype "passive"))
      (node (ref "U$1") (pin "TX0") (pinfunction "TX0_TX0") (pintype "bidirectional"))
    )
    (net (code "138") (name "TX1") (class "Default")
      (node (ref "U$1") (pin "TX1") (pinfunction "TX1_TX1") (pintype "bidirectional"))
    )
    (net (code "139") (name "X-DIR") (class "Default")
      (node (ref "STEPSTICK-X") (pin "DIR") (pinfunction "DIR_DIR") (pintype "bidirectional"))
      (node (ref "U$1") (pin "TX2") (pinfunction "TX2_TX2") (pintype "bidirectional"))
    )
    (net (code "140") (name "X-ENA") (class "Default")
      (node (ref "R3") (pin "2") (pinfunction "2_2") (pintype "passive"))
      (node (ref "STEPSTICK-X") (pin "ENABLE") (pinfunction "EN_ENABLE") (pintype "bidirectional"))
      (node (ref "U$1") (pin "22") (pinfunction "22_22") (pintype "bidirectional"))
    )
    (net (code "141") (name "X-MIN") (class "Default")
      (node (ref "C51") (pin "2") (pinfunction "2_2") (pintype "passive"))
      (node (ref "R16") (pin "1") (pinfunction "1_1") (pintype "passive"))
      (node (ref "U$1") (pin "38") (pinfunction "38_38") (pintype "bidirectional"))
    )
    (net (code "142") (name "X-STP") (class "Default")
      (node (ref "STEPSTICK-X") (pin "STP") (pinfunction "STEP_STP") (pintype "bidirectional"))
      (node (ref "U$1") (pin "RX2") (pinfunction "RX2_RX2") (pintype "bidirectional"))
    )
    (net (code "143") (name "Y-DIR") (class "Default")
      (node (ref "STEPSTICK-Y") (pin "DIR") (pinfunction "DIR_DIR") (pintype "bidirectional"))
      (node (ref "U$1") (pin "3") (pinfunction "3_3") (pintype "bidirectional"))
    )
    (net (code "144") (name "Y-ENA") (class "Default")
      (node (ref "R1") (pin "2") (pinfunction "2_2") (pintype "passive"))
      (node (ref "STEPSTICK-Y") (pin "ENABLE") (pinfunction "EN_ENABLE") (pintype "bidirectional"))
      (node (ref "U$1") (pin "26") (pinfunction "26_26") (pintype "bidirectional"))
    )
    (net (code "145") (name "Y-MIN") (class "Default")
      (node (ref "C49") (pin "2") (pinfunction "2_2") (pintype "passive"))
      (node (ref "R18") (pin "1") (pinfunction "1_1") (pintype "passive"))
      (node (ref "U$1") (pin "34") (pinfunction "34_34") (pintype "bidirectional"))
    )
    (net (code "146") (name "Y-STP") (class "Default")
      (node (ref "STEPSTICK-Y") (pin "STP") (pinfunction "STEP_STP") (pintype "bidirectional"))
      (node (ref "U$1") (pin "2") (pinfunction "2_2") (pintype "bidirectional"))
    )
    (net (code "147") (name "Z-DIR") (class "Default")
      (node (ref "STEPSTICK-Z1") (pin "DIR") (pinfunction "DIR_DIR") (pintype "bidirectional"))
      (node (ref "U$1") (pin "A9") (pinfunction "A9_A9") (pintype "bidirectional"))
    )
    (net (code "148") (name "Z-ENA") (class "Default")
      (node (ref "R5") (pin "2") (pinfunction "2_2") (pintype "passive"))
      (node (ref "STEPSTICK-Z1") (pin "ENABLE") (pinfunction "EN_ENABLE") (pintype "bidirectional"))
      (node (ref "U$1") (pin "RX3") (pinfunction "RX3_RX3") (pintype "bidirectional"))
    )
    (net (code "149") (name "Z-MIN") (class "Default")
      (node (ref "C32") (pin "2") (pinfunction "2_2") (pintype "passive"))
      (node (ref "R20") (pin "1") (pinfunction "1_1") (pintype "passive"))
      (node (ref "U$1") (pin "30") (pinfunction "30_30") (pintype "bidirectional"))
    )
    (net (code "150") (name "Z-STP") (class "Default")
      (node (ref "STEPSTICK-Z1") (pin "STP") (pinfunction "STEP_STP") (pintype "bidirectional"))
      (node (ref "U$1") (pin "A10") (pinfunction "A10_A10") (pintype "bidirectional"))
    )
    (net (code "151") (name "unconnected-(JP7-Pad1)") (class "Default")
      (node (ref "JP7") (pin "1") (pinfunction "1_1") (pintype "passive"))
    )
    (net (code "152") (name "unconnected-(SV5-Pad9)") (class "Default")
      (node (ref "SV5") (pin "9") (pinfunction "9_9") (pintype "passive"))
    )
    (net (code "153") (name "unconnected-(U$1-Pad5V)") (class "Default")
      (node (ref "U$1") (pin "5V") (pinfunction "5V_5V") (pintype "bidirectional"))
    )
    (net (code "154") (name "unconnected-(U$1-Pad8)") (class "Default")
      (node (ref "U$1") (pin "8") (pinfunction "8_8") (pintype "bidirectional"))
    )
    (net (code "155") (name "unconnected-(U$1-PadA5)") (class "Default")
      (node (ref "U$1") (pin "A5") (pinfunction "A5_A5") (pintype "bidirectional"))
    )
    (net (code "156") (name "unconnected-(U$1-PadAREF)") (class "Default")
      (node (ref "U$1") (pin "AREF") (pinfunction "AREF_AREF") (pintype "bidirectional"))
    )
    (net (code "157") (name "unconnected-(U$1-PadGND1)") (class "Default")
      (node (ref "U$1") (pin "GND1") (pinfunction "GND1_GND1") (pintype "bidirectional"))
    )
    (net (code "158") (name "unconnected-(U$1-PadNC)") (class "Default")
      (node (ref "U$1") (pin "NC") (pinfunction "NC_NC") (pintype "bidirectional"))
    )
    (net (code "159") (name "unconnected-(U$1-PadRESET)") (class "Default")
      (node (ref "U$1") (pin "RESET") (pinfunction "RESET_RESET") (pintype "bidirectional"))
    )
  )
)
